# SignalRouting.net
KiCad netlist of a schematic drawn in Altium Designer
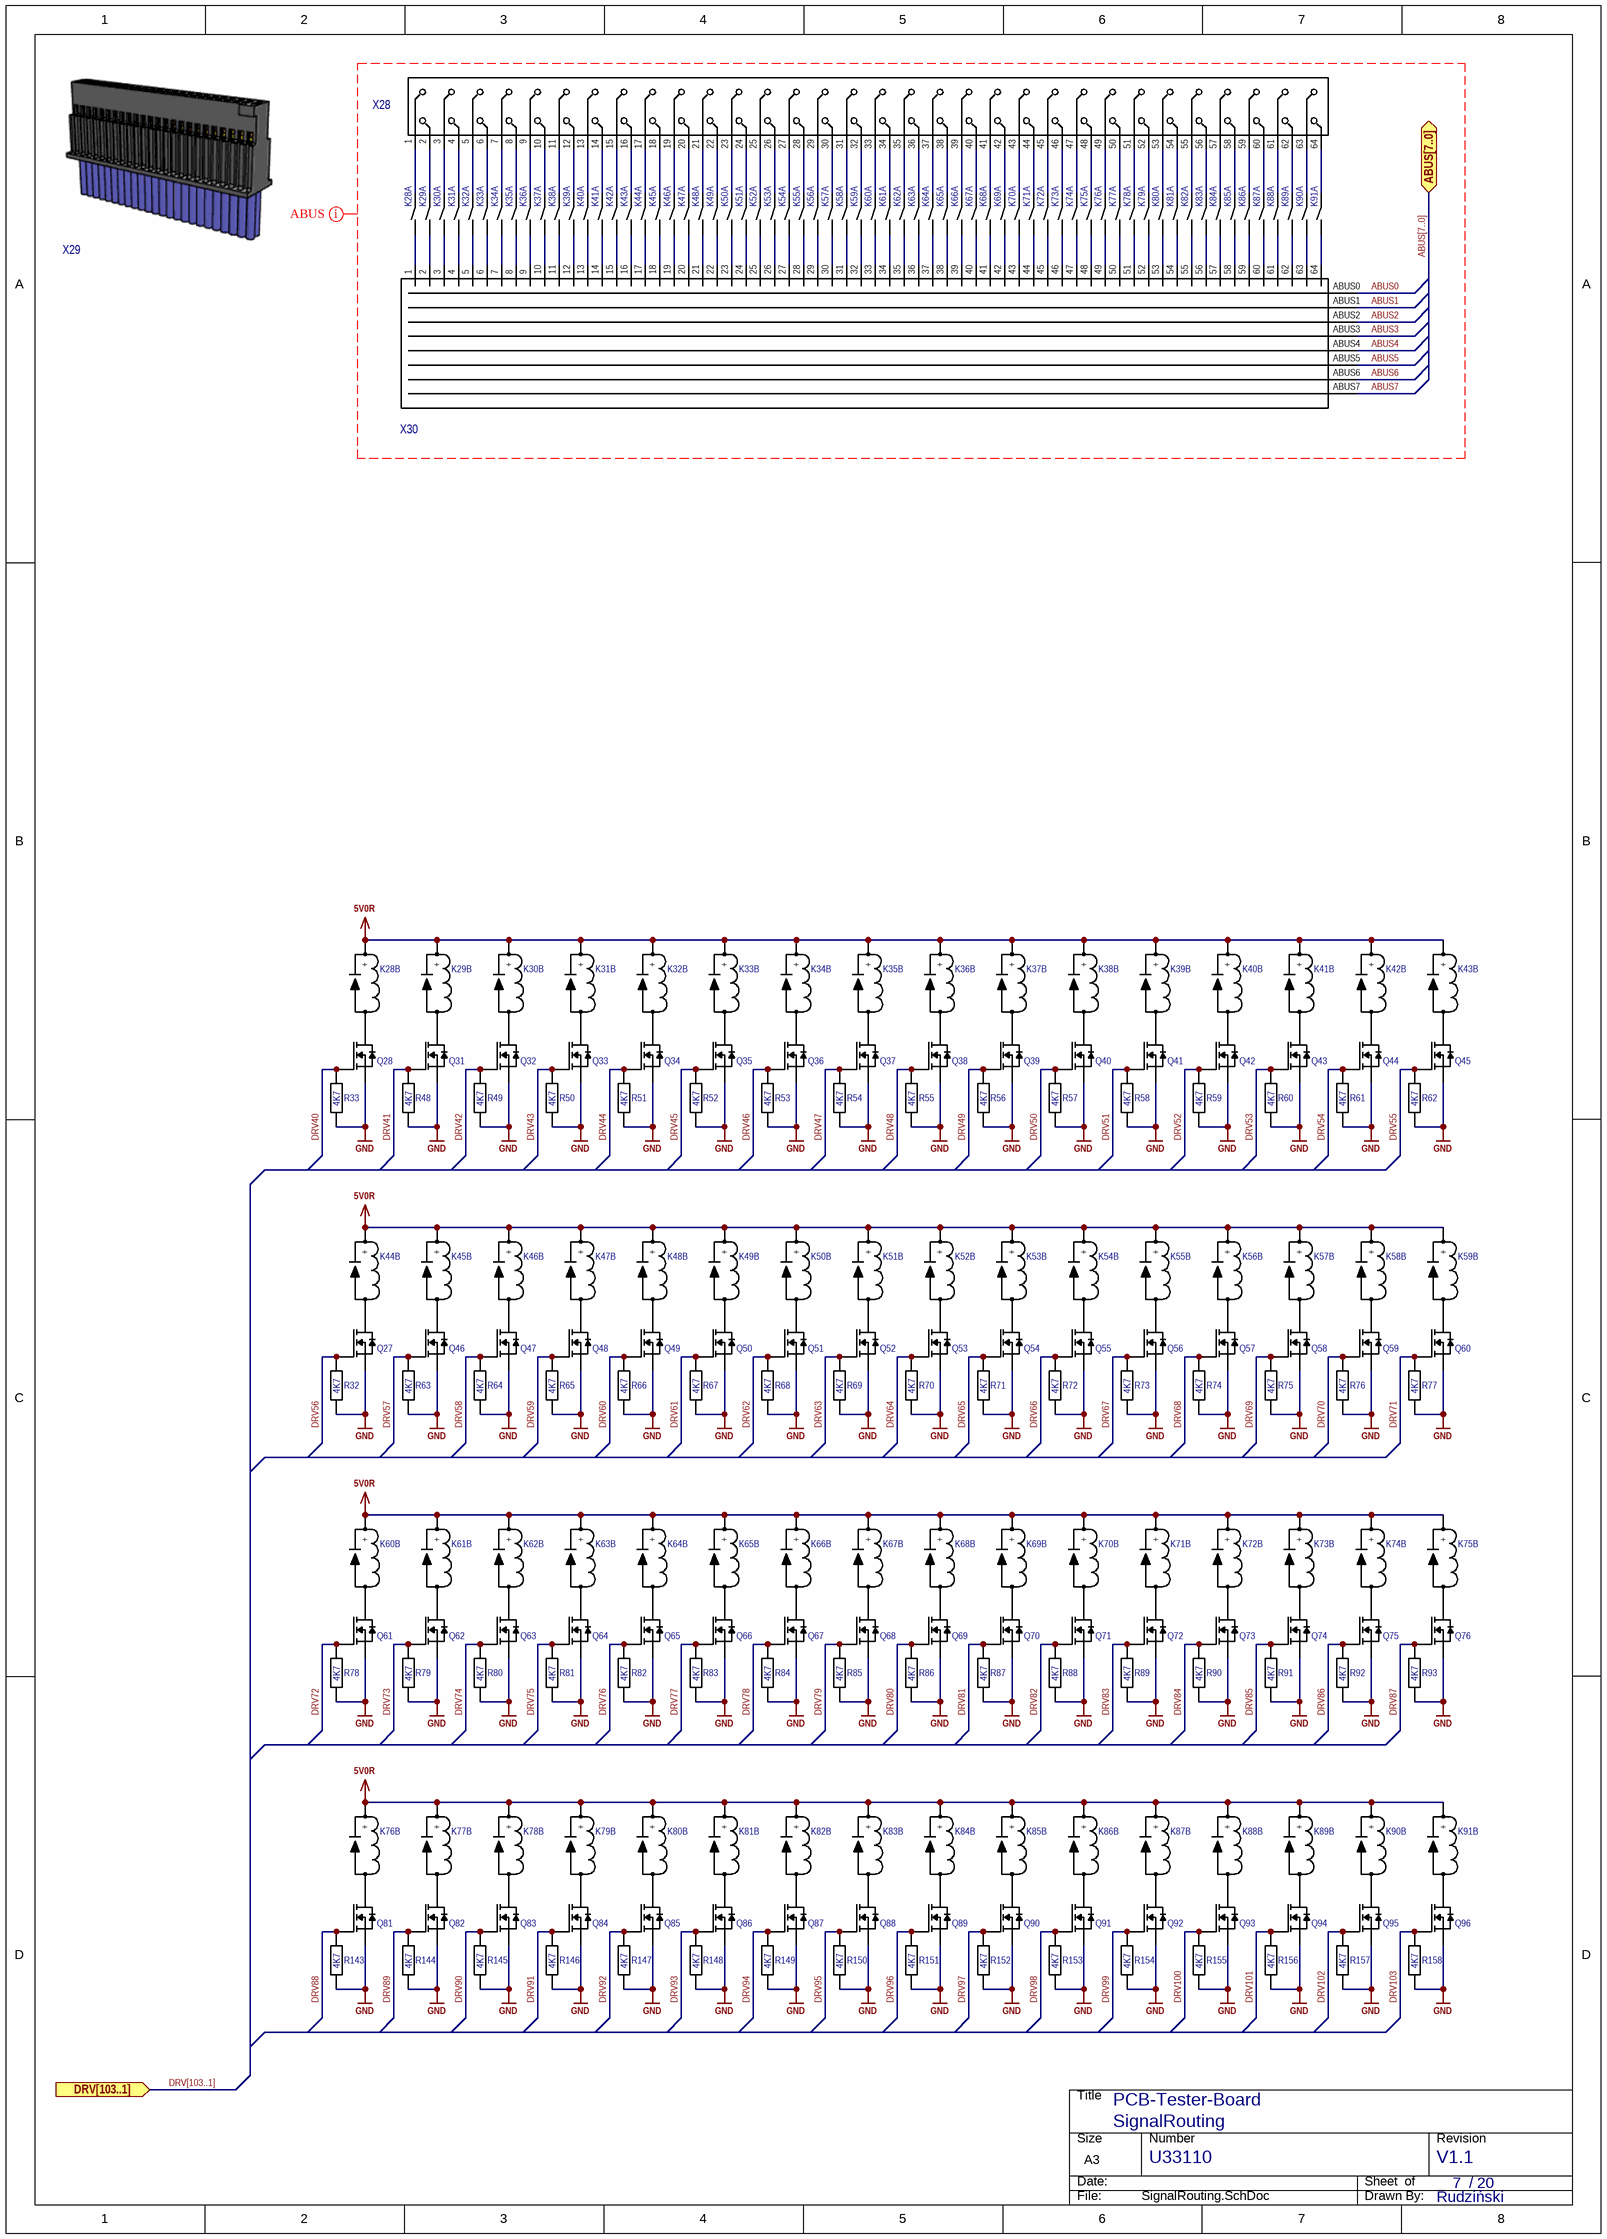
[diagram p0: SignalRouting.SchDoc]

(export (version "E")
  (design (tool "Eeschema 10.0.6"))
  (components
    (comp (ref "K28")
      (value "K")
      (footprint "118-1A")
      (description "5V Signal Relais, Normal Open")
      (fields
        (field (name "02. DISTRIBUTOR PART NUMBER") "118-1-A-5/2D")
        (field (name "13. CREATED DATE/NAME") "20.12.17 S. Kaiser")
      )
      (libsource (lib "chickenfood") (part "118-1-A-5/2D"))
    )
    (comp (ref "K29")
      (value "K")
      (footprint "118-1A")
      (description "5V Signal Relais, Normal Open")
      (fields
        (field (name "02. DISTRIBUTOR PART NUMBER") "118-1-A-5/2D")
        (field (name "13. CREATED DATE/NAME") "20.12.17 S. Kaiser")
      )
      (libsource (lib "chickenfood") (part "118-1-A-5/2D"))
    )
    (comp (ref "K30")
      (value "K")
      (footprint "118-1A")
      (description "5V Signal Relais, Normal Open")
      (fields
        (field (name "02. DISTRIBUTOR PART NUMBER") "118-1-A-5/2D")
        (field (name "13. CREATED DATE/NAME") "20.12.17 S. Kaiser")
      )
      (libsource (lib "") (part "118-1-A-5/2D_1"))
    )
    (comp (ref "K31")
      (value "K")
      (footprint "118-1A")
      (description "5V Signal Relais, Normal Open")
      (fields
        (field (name "02. DISTRIBUTOR PART NUMBER") "118-1-A-5/2D")
        (field (name "13. CREATED DATE/NAME") "20.12.17 S. Kaiser")
      )
      (libsource (lib "") (part "118-1-A-5/2D_1"))
    )
    (comp (ref "K32")
      (value "K")
      (footprint "118-1A")
      (description "5V Signal Relais, Normal Open")
      (fields
        (field (name "02. DISTRIBUTOR PART NUMBER") "118-1-A-5/2D")
        (field (name "13. CREATED DATE/NAME") "20.12.17 S. Kaiser")
      )
      (libsource (lib "") (part "118-1-A-5/2D_1"))
    )
    (comp (ref "K33")
      (value "K")
      (footprint "118-1A")
      (description "5V Signal Relais, Normal Open")
      (fields
        (field (name "02. DISTRIBUTOR PART NUMBER") "118-1-A-5/2D")
        (field (name "13. CREATED DATE/NAME") "20.12.17 S. Kaiser")
      )
      (libsource (lib "") (part "118-1-A-5/2D_1"))
    )
    (comp (ref "K34")
      (value "K")
      (footprint "118-1A")
      (description "5V Signal Relais, Normal Open")
      (fields
        (field (name "02. DISTRIBUTOR PART NUMBER") "118-1-A-5/2D")
        (field (name "13. CREATED DATE/NAME") "20.12.17 S. Kaiser")
      )
      (libsource (lib "chickenfood") (part "118-1-A-5/2D"))
    )
    (comp (ref "K35")
      (value "K")
      (footprint "118-1A")
      (description "5V Signal Relais, Normal Open")
      (fields
        (field (name "02. DISTRIBUTOR PART NUMBER") "118-1-A-5/2D")
        (field (name "13. CREATED DATE/NAME") "20.12.17 S. Kaiser")
      )
      (libsource (lib "") (part "118-1-A-5/2D_1"))
    )
    (comp (ref "K36")
      (value "K")
      (footprint "118-1A")
      (description "5V Signal Relais, Normal Open")
      (fields
        (field (name "02. DISTRIBUTOR PART NUMBER") "118-1-A-5/2D")
        (field (name "13. CREATED DATE/NAME") "20.12.17 S. Kaiser")
      )
      (libsource (lib "") (part "118-1-A-5/2D_1"))
    )
    (comp (ref "K37")
      (value "K")
      (footprint "118-1A")
      (description "5V Signal Relais, Normal Open")
      (fields
        (field (name "02. DISTRIBUTOR PART NUMBER") "118-1-A-5/2D")
        (field (name "13. CREATED DATE/NAME") "20.12.17 S. Kaiser")
      )
      (libsource (lib "chickenfood") (part "118-1-A-5/2D"))
    )
    (comp (ref "K38")
      (value "K")
      (footprint "118-1A")
      (description "5V Signal Relais, Normal Open")
      (fields
        (field (name "02. DISTRIBUTOR PART NUMBER") "118-1-A-5/2D")
        (field (name "13. CREATED DATE/NAME") "20.12.17 S. Kaiser")
      )
      (libsource (lib "") (part "118-1-A-5/2D_1"))
    )
    (comp (ref "K39")
      (value "K")
      (footprint "118-1A")
      (description "5V Signal Relais, Normal Open")
      (fields
        (field (name "02. DISTRIBUTOR PART NUMBER") "118-1-A-5/2D")
        (field (name "13. CREATED DATE/NAME") "20.12.17 S. Kaiser")
      )
      (libsource (lib "chickenfood") (part "118-1-A-5/2D"))
    )
    (comp (ref "K40")
      (value "K")
      (footprint "118-1A")
      (description "5V Signal Relais, Normal Open")
      (fields
        (field (name "02. DISTRIBUTOR PART NUMBER") "118-1-A-5/2D")
        (field (name "13. CREATED DATE/NAME") "20.12.17 S. Kaiser")
      )
      (libsource (lib "chickenfood") (part "118-1-A-5/2D"))
    )
    (comp (ref "K41")
      (value "K")
      (footprint "118-1A")
      (description "5V Signal Relais, Normal Open")
      (fields
        (field (name "02. DISTRIBUTOR PART NUMBER") "118-1-A-5/2D")
        (field (name "13. CREATED DATE/NAME") "20.12.17 S. Kaiser")
      )
      (libsource (lib "chickenfood") (part "118-1-A-5/2D"))
    )
    (comp (ref "K42")
      (value "K")
      (footprint "118-1A")
      (description "5V Signal Relais, Normal Open")
      (fields
        (field (name "02. DISTRIBUTOR PART NUMBER") "118-1-A-5/2D")
        (field (name "13. CREATED DATE/NAME") "20.12.17 S. Kaiser")
      )
      (libsource (lib "chickenfood") (part "118-1-A-5/2D"))
    )
    (comp (ref "K43")
      (value "K")
      (footprint "118-1A")
      (description "5V Signal Relais, Normal Open")
      (fields
        (field (name "02. DISTRIBUTOR PART NUMBER") "118-1-A-5/2D")
        (field (name "13. CREATED DATE/NAME") "20.12.17 S. Kaiser")
      )
      (libsource (lib "chickenfood") (part "118-1-A-5/2D"))
    )
    (comp (ref "K44")
      (value "K")
      (footprint "118-1A")
      (description "5V Signal Relais, Normal Open")
      (fields
        (field (name "02. DISTRIBUTOR PART NUMBER") "118-1-A-5/2D")
        (field (name "13. CREATED DATE/NAME") "20.12.17 S. Kaiser")
      )
      (libsource (lib "chickenfood") (part "118-1-A-5/2D"))
    )
    (comp (ref "K45")
      (value "K")
      (footprint "118-1A")
      (description "5V Signal Relais, Normal Open")
      (fields
        (field (name "02. DISTRIBUTOR PART NUMBER") "118-1-A-5/2D")
        (field (name "13. CREATED DATE/NAME") "20.12.17 S. Kaiser")
      )
      (libsource (lib "") (part "118-1-A-5/2D_1"))
    )
    (comp (ref "K46")
      (value "K")
      (footprint "118-1A")
      (description "5V Signal Relais, Normal Open")
      (fields
        (field (name "02. DISTRIBUTOR PART NUMBER") "118-1-A-5/2D")
        (field (name "13. CREATED DATE/NAME") "20.12.17 S. Kaiser")
      )
      (libsource (lib "") (part "118-1-A-5/2D_1"))
    )
    (comp (ref "K47")
      (value "K")
      (footprint "118-1A")
      (description "5V Signal Relais, Normal Open")
      (fields
        (field (name "02. DISTRIBUTOR PART NUMBER") "118-1-A-5/2D")
        (field (name "13. CREATED DATE/NAME") "20.12.17 S. Kaiser")
      )
      (libsource (lib "chickenfood") (part "118-1-A-5/2D"))
    )
    (comp (ref "K48")
      (value "K")
      (footprint "118-1A")
      (description "5V Signal Relais, Normal Open")
      (fields
        (field (name "02. DISTRIBUTOR PART NUMBER") "118-1-A-5/2D")
        (field (name "13. CREATED DATE/NAME") "20.12.17 S. Kaiser")
      )
      (libsource (lib "") (part "118-1-A-5/2D_1"))
    )
    (comp (ref "K49")
      (value "K")
      (footprint "118-1A")
      (description "5V Signal Relais, Normal Open")
      (fields
        (field (name "02. DISTRIBUTOR PART NUMBER") "118-1-A-5/2D")
        (field (name "13. CREATED DATE/NAME") "20.12.17 S. Kaiser")
      )
      (libsource (lib "chickenfood") (part "118-1-A-5/2D"))
    )
    (comp (ref "K50")
      (value "K")
      (footprint "118-1A")
      (description "5V Signal Relais, Normal Open")
      (fields
        (field (name "02. DISTRIBUTOR PART NUMBER") "118-1-A-5/2D")
        (field (name "13. CREATED DATE/NAME") "20.12.17 S. Kaiser")
      )
      (libsource (lib "chickenfood") (part "118-1-A-5/2D"))
    )
    (comp (ref "K51")
      (value "K")
      (footprint "118-1A")
      (description "5V Signal Relais, Normal Open")
      (fields
        (field (name "02. DISTRIBUTOR PART NUMBER") "118-1-A-5/2D")
        (field (name "13. CREATED DATE/NAME") "20.12.17 S. Kaiser")
      )
      (libsource (lib "") (part "118-1-A-5/2D_1"))
    )
    (comp (ref "K52")
      (value "K")
      (footprint "118-1A")
      (description "5V Signal Relais, Normal Open")
      (fields
        (field (name "02. DISTRIBUTOR PART NUMBER") "118-1-A-5/2D")
        (field (name "13. CREATED DATE/NAME") "20.12.17 S. Kaiser")
      )
      (libsource (lib "chickenfood") (part "118-1-A-5/2D"))
    )
    (comp (ref "K53")
      (value "K")
      (footprint "118-1A")
      (description "5V Signal Relais, Normal Open")
      (fields
        (field (name "02. DISTRIBUTOR PART NUMBER") "118-1-A-5/2D")
        (field (name "13. CREATED DATE/NAME") "20.12.17 S. Kaiser")
      )
      (libsource (lib "chickenfood") (part "118-1-A-5/2D"))
    )
    (comp (ref "K54")
      (value "K")
      (footprint "118-1A")
      (description "5V Signal Relais, Normal Open")
      (fields
        (field (name "02. DISTRIBUTOR PART NUMBER") "118-1-A-5/2D")
        (field (name "13. CREATED DATE/NAME") "20.12.17 S. Kaiser")
      )
      (libsource (lib "") (part "118-1-A-5/2D_1"))
    )
    (comp (ref "K55")
      (value "K")
      (footprint "118-1A")
      (description "5V Signal Relais, Normal Open")
      (fields
        (field (name "02. DISTRIBUTOR PART NUMBER") "118-1-A-5/2D")
        (field (name "13. CREATED DATE/NAME") "20.12.17 S. Kaiser")
      )
      (libsource (lib "chickenfood") (part "118-1-A-5/2D"))
    )
    (comp (ref "K56")
      (value "K")
      (footprint "118-1A")
      (description "5V Signal Relais, Normal Open")
      (fields
        (field (name "02. DISTRIBUTOR PART NUMBER") "118-1-A-5/2D")
        (field (name "13. CREATED DATE/NAME") "20.12.17 S. Kaiser")
      )
      (libsource (lib "") (part "118-1-A-5/2D_1"))
    )
    (comp (ref "K57")
      (value "K")
      (footprint "118-1A")
      (description "5V Signal Relais, Normal Open")
      (fields
        (field (name "02. DISTRIBUTOR PART NUMBER") "118-1-A-5/2D")
        (field (name "13. CREATED DATE/NAME") "20.12.17 S. Kaiser")
      )
      (libsource (lib "") (part "118-1-A-5/2D_1"))
    )
    (comp (ref "K58")
      (value "K")
      (footprint "118-1A")
      (description "5V Signal Relais, Normal Open")
      (fields
        (field (name "02. DISTRIBUTOR PART NUMBER") "118-1-A-5/2D")
        (field (name "13. CREATED DATE/NAME") "20.12.17 S. Kaiser")
      )
      (libsource (lib "chickenfood") (part "118-1-A-5/2D"))
    )
    (comp (ref "K59")
      (value "K")
      (footprint "118-1A")
      (description "5V Signal Relais, Normal Open")
      (fields
        (field (name "02. DISTRIBUTOR PART NUMBER") "118-1-A-5/2D")
        (field (name "13. CREATED DATE/NAME") "20.12.17 S. Kaiser")
      )
      (libsource (lib "chickenfood") (part "118-1-A-5/2D"))
    )
    (comp (ref "K60")
      (value "K")
      (footprint "118-1A")
      (description "5V Signal Relais, Normal Open")
      (fields
        (field (name "02. DISTRIBUTOR PART NUMBER") "118-1-A-5/2D")
        (field (name "13. CREATED DATE/NAME") "20.12.17 S. Kaiser")
      )
      (libsource (lib "") (part "118-1-A-5/2D_1"))
    )
    (comp (ref "K61")
      (value "K")
      (footprint "118-1A")
      (description "5V Signal Relais, Normal Open")
      (fields
        (field (name "02. DISTRIBUTOR PART NUMBER") "118-1-A-5/2D")
        (field (name "13. CREATED DATE/NAME") "20.12.17 S. Kaiser")
      )
      (libsource (lib "chickenfood") (part "118-1-A-5/2D"))
    )
    (comp (ref "K62")
      (value "K")
      (footprint "118-1A")
      (description "5V Signal Relais, Normal Open")
      (fields
        (field (name "02. DISTRIBUTOR PART NUMBER") "118-1-A-5/2D")
        (field (name "13. CREATED DATE/NAME") "20.12.17 S. Kaiser")
      )
      (libsource (lib "") (part "118-1-A-5/2D_1"))
    )
    (comp (ref "K63")
      (value "K")
      (footprint "118-1A")
      (description "5V Signal Relais, Normal Open")
      (fields
        (field (name "02. DISTRIBUTOR PART NUMBER") "118-1-A-5/2D")
        (field (name "13. CREATED DATE/NAME") "20.12.17 S. Kaiser")
      )
      (libsource (lib "chickenfood") (part "118-1-A-5/2D"))
    )
    (comp (ref "K64")
      (value "K")
      (footprint "118-1A")
      (description "5V Signal Relais, Normal Open")
      (fields
        (field (name "02. DISTRIBUTOR PART NUMBER") "118-1-A-5/2D")
        (field (name "13. CREATED DATE/NAME") "20.12.17 S. Kaiser")
      )
      (libsource (lib "chickenfood") (part "118-1-A-5/2D"))
    )
    (comp (ref "K65")
      (value "K")
      (footprint "118-1A")
      (description "5V Signal Relais, Normal Open")
      (fields
        (field (name "02. DISTRIBUTOR PART NUMBER") "118-1-A-5/2D")
        (field (name "13. CREATED DATE/NAME") "20.12.17 S. Kaiser")
      )
      (libsource (lib "chickenfood") (part "118-1-A-5/2D"))
    )
    (comp (ref "K66")
      (value "K")
      (footprint "118-1A")
      (description "5V Signal Relais, Normal Open")
      (fields
        (field (name "02. DISTRIBUTOR PART NUMBER") "118-1-A-5/2D")
        (field (name "13. CREATED DATE/NAME") "20.12.17 S. Kaiser")
      )
      (libsource (lib "chickenfood") (part "118-1-A-5/2D"))
    )
    (comp (ref "K67")
      (value "K")
      (footprint "118-1A")
      (description "5V Signal Relais, Normal Open")
      (fields
        (field (name "02. DISTRIBUTOR PART NUMBER") "118-1-A-5/2D")
        (field (name "13. CREATED DATE/NAME") "20.12.17 S. Kaiser")
      )
      (libsource (lib "chickenfood") (part "118-1-A-5/2D"))
    )
    (comp (ref "K68")
      (value "K")
      (footprint "118-1A")
      (description "5V Signal Relais, Normal Open")
      (fields
        (field (name "02. DISTRIBUTOR PART NUMBER") "118-1-A-5/2D")
        (field (name "13. CREATED DATE/NAME") "20.12.17 S. Kaiser")
      )
      (libsource (lib "chickenfood") (part "118-1-A-5/2D"))
    )
    (comp (ref "K69")
      (value "K")
      (footprint "118-1A")
      (description "5V Signal Relais, Normal Open")
      (fields
        (field (name "02. DISTRIBUTOR PART NUMBER") "118-1-A-5/2D")
        (field (name "13. CREATED DATE/NAME") "20.12.17 S. Kaiser")
      )
      (libsource (lib "chickenfood") (part "118-1-A-5/2D"))
    )
    (comp (ref "K70")
      (value "K")
      (footprint "118-1A")
      (description "5V Signal Relais, Normal Open")
      (fields
        (field (name "02. DISTRIBUTOR PART NUMBER") "118-1-A-5/2D")
        (field (name "13. CREATED DATE/NAME") "20.12.17 S. Kaiser")
      )
      (libsource (lib "") (part "118-1-A-5/2D_1"))
    )
    (comp (ref "K71")
      (value "K")
      (footprint "118-1A")
      (description "5V Signal Relais, Normal Open")
      (fields
        (field (name "02. DISTRIBUTOR PART NUMBER") "118-1-A-5/2D")
        (field (name "13. CREATED DATE/NAME") "20.12.17 S. Kaiser")
      )
      (libsource (lib "") (part "118-1-A-5/2D_1"))
    )
    (comp (ref "K72")
      (value "K")
      (footprint "118-1A")
      (description "5V Signal Relais, Normal Open")
      (fields
        (field (name "02. DISTRIBUTOR PART NUMBER") "118-1-A-5/2D")
        (field (name "13. CREATED DATE/NAME") "20.12.17 S. Kaiser")
      )
      (libsource (lib "") (part "118-1-A-5/2D_1"))
    )
    (comp (ref "K73")
      (value "K")
      (footprint "118-1A")
      (description "5V Signal Relais, Normal Open")
      (fields
        (field (name "02. DISTRIBUTOR PART NUMBER") "118-1-A-5/2D")
        (field (name "13. CREATED DATE/NAME") "20.12.17 S. Kaiser")
      )
      (libsource (lib "chickenfood") (part "118-1-A-5/2D"))
    )
    (comp (ref "K74")
      (value "K")
      (footprint "118-1A")
      (description "5V Signal Relais, Normal Open")
      (fields
        (field (name "02. DISTRIBUTOR PART NUMBER") "118-1-A-5/2D")
        (field (name "13. CREATED DATE/NAME") "20.12.17 S. Kaiser")
      )
      (libsource (lib "chickenfood") (part "118-1-A-5/2D"))
    )
    (comp (ref "K75")
      (value "K")
      (footprint "118-1A")
      (description "5V Signal Relais, Normal Open")
      (fields
        (field (name "02. DISTRIBUTOR PART NUMBER") "118-1-A-5/2D")
        (field (name "13. CREATED DATE/NAME") "20.12.17 S. Kaiser")
      )
      (libsource (lib "chickenfood") (part "118-1-A-5/2D"))
    )
    (comp (ref "K76")
      (value "K")
      (footprint "118-1A")
      (description "5V Signal Relais, Normal Open")
      (fields
        (field (name "02. DISTRIBUTOR PART NUMBER") "118-1-A-5/2D")
        (field (name "13. CREATED DATE/NAME") "20.12.17 S. Kaiser")
      )
      (libsource (lib "") (part "118-1-A-5/2D_1"))
    )
    (comp (ref "K77")
      (value "K")
      (footprint "118-1A")
      (description "5V Signal Relais, Normal Open")
      (fields
        (field (name "02. DISTRIBUTOR PART NUMBER") "118-1-A-5/2D")
        (field (name "13. CREATED DATE/NAME") "20.12.17 S. Kaiser")
      )
      (libsource (lib "") (part "118-1-A-5/2D_1"))
    )
    (comp (ref "K78")
      (value "K")
      (footprint "118-1A")
      (description "5V Signal Relais, Normal Open")
      (fields
        (field (name "02. DISTRIBUTOR PART NUMBER") "118-1-A-5/2D")
        (field (name "13. CREATED DATE/NAME") "20.12.17 S. Kaiser")
      )
      (libsource (lib "") (part "118-1-A-5/2D_1"))
    )
    (comp (ref "K79")
      (value "K")
      (footprint "118-1A")
      (description "5V Signal Relais, Normal Open")
      (fields
        (field (name "02. DISTRIBUTOR PART NUMBER") "118-1-A-5/2D")
        (field (name "13. CREATED DATE/NAME") "20.12.17 S. Kaiser")
      )
      (libsource (lib "chickenfood") (part "118-1-A-5/2D"))
    )
    (comp (ref "K80")
      (value "K")
      (footprint "118-1A")
      (description "5V Signal Relais, Normal Open")
      (fields
        (field (name "02. DISTRIBUTOR PART NUMBER") "118-1-A-5/2D")
        (field (name "13. CREATED DATE/NAME") "20.12.17 S. Kaiser")
      )
      (libsource (lib "") (part "118-1-A-5/2D_1"))
    )
    (comp (ref "K81")
      (value "K")
      (footprint "118-1A")
      (description "5V Signal Relais, Normal Open")
      (fields
        (field (name "02. DISTRIBUTOR PART NUMBER") "118-1-A-5/2D")
        (field (name "13. CREATED DATE/NAME") "20.12.17 S. Kaiser")
      )
      (libsource (lib "chickenfood") (part "118-1-A-5/2D"))
    )
    (comp (ref "K82")
      (value "K")
      (footprint "118-1A")
      (description "5V Signal Relais, Normal Open")
      (fields
        (field (name "02. DISTRIBUTOR PART NUMBER") "118-1-A-5/2D")
        (field (name "13. CREATED DATE/NAME") "20.12.17 S. Kaiser")
      )
      (libsource (lib "chickenfood") (part "118-1-A-5/2D"))
    )
    (comp (ref "K83")
      (value "K")
      (footprint "118-1A")
      (description "5V Signal Relais, Normal Open")
      (fields
        (field (name "02. DISTRIBUTOR PART NUMBER") "118-1-A-5/2D")
        (field (name "13. CREATED DATE/NAME") "20.12.17 S. Kaiser")
      )
      (libsource (lib "") (part "118-1-A-5/2D_1"))
    )
    (comp (ref "K84")
      (value "K")
      (footprint "118-1A")
      (description "5V Signal Relais, Normal Open")
      (fields
        (field (name "02. DISTRIBUTOR PART NUMBER") "118-1-A-5/2D")
        (field (name "13. CREATED DATE/NAME") "20.12.17 S. Kaiser")
      )
      (libsource (lib "") (part "118-1-A-5/2D_1"))
    )
    (comp (ref "K85")
      (value "K")
      (footprint "118-1A")
      (description "5V Signal Relais, Normal Open")
      (fields
        (field (name "02. DISTRIBUTOR PART NUMBER") "118-1-A-5/2D")
        (field (name "13. CREATED DATE/NAME") "20.12.17 S. Kaiser")
      )
      (libsource (lib "chickenfood") (part "118-1-A-5/2D"))
    )
    (comp (ref "K86")
      (value "K")
      (footprint "118-1A")
      (description "5V Signal Relais, Normal Open")
      (fields
        (field (name "02. DISTRIBUTOR PART NUMBER") "118-1-A-5/2D")
        (field (name "13. CREATED DATE/NAME") "20.12.17 S. Kaiser")
      )
      (libsource (lib "chickenfood") (part "118-1-A-5/2D"))
    )
    (comp (ref "K87")
      (value "K")
      (footprint "118-1A")
      (description "5V Signal Relais, Normal Open")
      (fields
        (field (name "02. DISTRIBUTOR PART NUMBER") "118-1-A-5/2D")
        (field (name "13. CREATED DATE/NAME") "20.12.17 S. Kaiser")
      )
      (libsource (lib "") (part "118-1-A-5/2D_1"))
    )
    (comp (ref "K88")
      (value "K")
      (footprint "118-1A")
      (description "5V Signal Relais, Normal Open")
      (fields
        (field (name "02. DISTRIBUTOR PART NUMBER") "118-1-A-5/2D")
        (field (name "13. CREATED DATE/NAME") "20.12.17 S. Kaiser")
      )
      (libsource (lib "") (part "118-1-A-5/2D_1"))
    )
    (comp (ref "K89")
      (value "K")
      (footprint "118-1A")
      (description "5V Signal Relais, Normal Open")
      (fields
        (field (name "02. DISTRIBUTOR PART NUMBER") "118-1-A-5/2D")
        (field (name "13. CREATED DATE/NAME") "20.12.17 S. Kaiser")
      )
      (libsource (lib "") (part "118-1-A-5/2D_1"))
    )
    (comp (ref "K90")
      (value "K")
      (footprint "118-1A")
      (description "5V Signal Relais, Normal Open")
      (fields
        (field (name "02. DISTRIBUTOR PART NUMBER") "118-1-A-5/2D")
        (field (name "13. CREATED DATE/NAME") "20.12.17 S. Kaiser")
      )
      (libsource (lib "") (part "118-1-A-5/2D_1"))
    )
    (comp (ref "K91")
      (value "K")
      (footprint "118-1A")
      (description "5V Signal Relais, Normal Open")
      (fields
        (field (name "02. DISTRIBUTOR PART NUMBER") "118-1-A-5/2D")
        (field (name "13. CREATED DATE/NAME") "20.12.17 S. Kaiser")
      )
      (libsource (lib "chickenfood") (part "118-1-A-5/2D"))
    )
    (comp (ref "Q27")
      (value "Q")
      (footprint "SOT23-3")
      (description "MOSFET N-CH 25V 680MA SOT-23")
      (fields
        (field (name "02. DISTRIBUTOR PART NUMBER") "FDV303NDKR-ND")
        (field (name "07. MANUFACTURER  PART NUMBER") "FDV303N")
        (field (name "13. CREATED DATE/NAME") "AUG 2018 / Hören")
      )
      (libsource (lib "SCT8-Board1") (part "FDV303N"))
    )
    (comp (ref "Q28")
      (value "Q")
      (footprint "SOT23-3")
      (description "MOSFET N-CH 25V 680MA SOT-23")
      (fields
        (field (name "02. DISTRIBUTOR PART NUMBER") "FDV303NDKR-ND")
        (field (name "07. MANUFACTURER  PART NUMBER") "FDV303N")
        (field (name "13. CREATED DATE/NAME") "AUG 2018 / Hören")
      )
      (libsource (lib "SCT8-Board1") (part "FDV303N"))
    )
    (comp (ref "Q31")
      (value "Q")
      (footprint "SOT23-3")
      (description "MOSFET N-CH 25V 680MA SOT-23")
      (fields
        (field (name "02. DISTRIBUTOR PART NUMBER") "FDV303NDKR-ND")
        (field (name "07. MANUFACTURER  PART NUMBER") "FDV303N")
        (field (name "13. CREATED DATE/NAME") "AUG 2018 / Hören")
      )
      (libsource (lib "SCT8-Board1") (part "FDV303N"))
    )
    (comp (ref "Q32")
      (value "Q")
      (footprint "SOT23-3")
      (description "MOSFET N-CH 25V 680MA SOT-23")
      (fields
        (field (name "02. DISTRIBUTOR PART NUMBER") "FDV303NDKR-ND")
        (field (name "07. MANUFACTURER  PART NUMBER") "FDV303N")
        (field (name "13. CREATED DATE/NAME") "AUG 2018 / Hören")
      )
      (libsource (lib "SCT8-Board1") (part "FDV303N"))
    )
    (comp (ref "Q33")
      (value "Q")
      (footprint "SOT23-3")
      (description "MOSFET N-CH 25V 680MA SOT-23")
      (fields
        (field (name "02. DISTRIBUTOR PART NUMBER") "FDV303NDKR-ND")
        (field (name "07. MANUFACTURER  PART NUMBER") "FDV303N")
        (field (name "13. CREATED DATE/NAME") "AUG 2018 / Hören")
      )
      (libsource (lib "SCT8-Board1") (part "FDV303N"))
    )
    (comp (ref "Q34")
      (value "Q")
      (footprint "SOT23-3")
      (description "MOSFET N-CH 25V 680MA SOT-23")
      (fields
        (field (name "02. DISTRIBUTOR PART NUMBER") "FDV303NDKR-ND")
        (field (name "07. MANUFACTURER  PART NUMBER") "FDV303N")
        (field (name "13. CREATED DATE/NAME") "AUG 2018 / Hören")
      )
      (libsource (lib "SCT8-Board1") (part "FDV303N"))
    )
    (comp (ref "Q35")
      (value "Q")
      (footprint "SOT23-3")
      (description "MOSFET N-CH 25V 680MA SOT-23")
      (fields
        (field (name "02. DISTRIBUTOR PART NUMBER") "FDV303NDKR-ND")
        (field (name "07. MANUFACTURER  PART NUMBER") "FDV303N")
        (field (name "13. CREATED DATE/NAME") "AUG 2018 / Hören")
      )
      (libsource (lib "SCT8-Board1") (part "FDV303N"))
    )
    (comp (ref "Q36")
      (value "Q")
      (footprint "SOT23-3")
      (description "MOSFET N-CH 25V 680MA SOT-23")
      (fields
        (field (name "02. DISTRIBUTOR PART NUMBER") "FDV303NDKR-ND")
        (field (name "07. MANUFACTURER  PART NUMBER") "FDV303N")
        (field (name "13. CREATED DATE/NAME") "AUG 2018 / Hören")
      )
      (libsource (lib "SCT8-Board1") (part "FDV303N"))
    )
    (comp (ref "Q37")
      (value "Q")
      (footprint "SOT23-3")
      (description "MOSFET N-CH 25V 680MA SOT-23")
      (fields
        (field (name "02. DISTRIBUTOR PART NUMBER") "FDV303NDKR-ND")
        (field (name "07. MANUFACTURER  PART NUMBER") "FDV303N")
        (field (name "13. CREATED DATE/NAME") "AUG 2018 / Hören")
      )
      (libsource (lib "SCT8-Board1") (part "FDV303N"))
    )
    (comp (ref "Q38")
      (value "Q")
      (footprint "SOT23-3")
      (description "MOSFET N-CH 25V 680MA SOT-23")
      (fields
        (field (name "02. DISTRIBUTOR PART NUMBER") "FDV303NDKR-ND")
        (field (name "07. MANUFACTURER  PART NUMBER") "FDV303N")
        (field (name "13. CREATED DATE/NAME") "AUG 2018 / Hören")
      )
      (libsource (lib "SCT8-Board1") (part "FDV303N"))
    )
    (comp (ref "Q39")
      (value "Q")
      (footprint "SOT23-3")
      (description "MOSFET N-CH 25V 680MA SOT-23")
      (fields
        (field (name "02. DISTRIBUTOR PART NUMBER") "FDV303NDKR-ND")
        (field (name "07. MANUFACTURER  PART NUMBER") "FDV303N")
        (field (name "13. CREATED DATE/NAME") "AUG 2018 / Hören")
      )
      (libsource (lib "SCT8-Board1") (part "FDV303N"))
    )
    (comp (ref "Q40")
      (value "Q")
      (footprint "SOT23-3")
      (description "MOSFET N-CH 25V 680MA SOT-23")
      (fields
        (field (name "02. DISTRIBUTOR PART NUMBER") "FDV303NDKR-ND")
        (field (name "07. MANUFACTURER  PART NUMBER") "FDV303N")
        (field (name "13. CREATED DATE/NAME") "AUG 2018 / Hören")
      )
      (libsource (lib "SCT8-Board1") (part "FDV303N"))
    )
    (comp (ref "Q41")
      (value "Q")
      (footprint "SOT23-3")
      (description "MOSFET N-CH 25V 680MA SOT-23")
      (fields
        (field (name "02. DISTRIBUTOR PART NUMBER") "FDV303NDKR-ND")
        (field (name "07. MANUFACTURER  PART NUMBER") "FDV303N")
        (field (name "13. CREATED DATE/NAME") "AUG 2018 / Hören")
      )
      (libsource (lib "SCT8-Board1") (part "FDV303N"))
    )
    (comp (ref "Q42")
      (value "Q")
      (footprint "SOT23-3")
      (description "MOSFET N-CH 25V 680MA SOT-23")
      (fields
        (field (name "02. DISTRIBUTOR PART NUMBER") "FDV303NDKR-ND")
        (field (name "07. MANUFACTURER  PART NUMBER") "FDV303N")
        (field (name "13. CREATED DATE/NAME") "AUG 2018 / Hören")
      )
      (libsource (lib "SCT8-Board1") (part "FDV303N"))
    )
    (comp (ref "Q43")
      (value "Q")
      (footprint "SOT23-3")
      (description "MOSFET N-CH 25V 680MA SOT-23")
      (fields
        (field (name "02. DISTRIBUTOR PART NUMBER") "FDV303NDKR-ND")
        (field (name "07. MANUFACTURER  PART NUMBER") "FDV303N")
        (field (name "13. CREATED DATE/NAME") "AUG 2018 / Hören")
      )
      (libsource (lib "SCT8-Board1") (part "FDV303N"))
    )
    (comp (ref "Q44")
      (value "Q")
      (footprint "SOT23-3")
      (description "MOSFET N-CH 25V 680MA SOT-23")
      (fields
        (field (name "02. DISTRIBUTOR PART NUMBER") "FDV303NDKR-ND")
        (field (name "07. MANUFACTURER  PART NUMBER") "FDV303N")
        (field (name "13. CREATED DATE/NAME") "AUG 2018 / Hören")
      )
      (libsource (lib "SCT8-Board1") (part "FDV303N"))
    )
    (comp (ref "Q45")
      (value "Q")
      (footprint "SOT23-3")
      (description "MOSFET N-CH 25V 680MA SOT-23")
      (fields
        (field (name "02. DISTRIBUTOR PART NUMBER") "FDV303NDKR-ND")
        (field (name "07. MANUFACTURER  PART NUMBER") "FDV303N")
        (field (name "13. CREATED DATE/NAME") "AUG 2018 / Hören")
      )
      (libsource (lib "SCT8-Board1") (part "FDV303N"))
    )
    (comp (ref "Q46")
      (value "Q")
      (footprint "SOT23-3")
      (description "MOSFET N-CH 25V 680MA SOT-23")
      (fields
        (field (name "02. DISTRIBUTOR PART NUMBER") "FDV303NDKR-ND")
        (field (name "07. MANUFACTURER  PART NUMBER") "FDV303N")
        (field (name "13. CREATED DATE/NAME") "AUG 2018 / Hören")
      )
      (libsource (lib "SCT8-Board1") (part "FDV303N"))
    )
    (comp (ref "Q47")
      (value "Q")
      (footprint "SOT23-3")
      (description "MOSFET N-CH 25V 680MA SOT-23")
      (fields
        (field (name "02. DISTRIBUTOR PART NUMBER") "FDV303NDKR-ND")
        (field (name "07. MANUFACTURER  PART NUMBER") "FDV303N")
        (field (name "13. CREATED DATE/NAME") "AUG 2018 / Hören")
      )
      (libsource (lib "SCT8-Board1") (part "FDV303N"))
    )
    (comp (ref "Q48")
      (value "Q")
      (footprint "SOT23-3")
      (description "MOSFET N-CH 25V 680MA SOT-23")
      (fields
        (field (name "02. DISTRIBUTOR PART NUMBER") "FDV303NDKR-ND")
        (field (name "07. MANUFACTURER  PART NUMBER") "FDV303N")
        (field (name "13. CREATED DATE/NAME") "AUG 2018 / Hören")
      )
      (libsource (lib "SCT8-Board1") (part "FDV303N"))
    )
    (comp (ref "Q49")
      (value "Q")
      (footprint "SOT23-3")
      (description "MOSFET N-CH 25V 680MA SOT-23")
      (fields
        (field (name "02. DISTRIBUTOR PART NUMBER") "FDV303NDKR-ND")
        (field (name "07. MANUFACTURER  PART NUMBER") "FDV303N")
        (field (name "13. CREATED DATE/NAME") "AUG 2018 / Hören")
      )
      (libsource (lib "SCT8-Board1") (part "FDV303N"))
    )
    (comp (ref "Q50")
      (value "Q")
      (footprint "SOT23-3")
      (description "MOSFET N-CH 25V 680MA SOT-23")
      (fields
        (field (name "02. DISTRIBUTOR PART NUMBER") "FDV303NDKR-ND")
        (field (name "07. MANUFACTURER  PART NUMBER") "FDV303N")
        (field (name "13. CREATED DATE/NAME") "AUG 2018 / Hören")
      )
      (libsource (lib "SCT8-Board1") (part "FDV303N"))
    )
    (comp (ref "Q51")
      (value "Q")
      (footprint "SOT23-3")
      (description "MOSFET N-CH 25V 680MA SOT-23")
      (fields
        (field (name "02. DISTRIBUTOR PART NUMBER") "FDV303NDKR-ND")
        (field (name "07. MANUFACTURER  PART NUMBER") "FDV303N")
        (field (name "13. CREATED DATE/NAME") "AUG 2018 / Hören")
      )
      (libsource (lib "SCT8-Board1") (part "FDV303N"))
    )
    (comp (ref "Q52")
      (value "Q")
      (footprint "SOT23-3")
      (description "MOSFET N-CH 25V 680MA SOT-23")
      (fields
        (field (name "02. DISTRIBUTOR PART NUMBER") "FDV303NDKR-ND")
        (field (name "07. MANUFACTURER  PART NUMBER") "FDV303N")
        (field (name "13. CREATED DATE/NAME") "AUG 2018 / Hören")
      )
      (libsource (lib "SCT8-Board1") (part "FDV303N"))
    )
    (comp (ref "Q53")
      (value "Q")
      (footprint "SOT23-3")
      (description "MOSFET N-CH 25V 680MA SOT-23")
      (fields
        (field (name "02. DISTRIBUTOR PART NUMBER") "FDV303NDKR-ND")
        (field (name "07. MANUFACTURER  PART NUMBER") "FDV303N")
        (field (name "13. CREATED DATE/NAME") "AUG 2018 / Hören")
      )
      (libsource (lib "SCT8-Board1") (part "FDV303N"))
    )
    (comp (ref "Q54")
      (value "Q")
      (footprint "SOT23-3")
      (description "MOSFET N-CH 25V 680MA SOT-23")
      (fields
        (field (name "02. DISTRIBUTOR PART NUMBER") "FDV303NDKR-ND")
        (field (name "07. MANUFACTURER  PART NUMBER") "FDV303N")
        (field (name "13. CREATED DATE/NAME") "AUG 2018 / Hören")
      )
      (libsource (lib "SCT8-Board1") (part "FDV303N"))
    )
    (comp (ref "Q55")
      (value "Q")
      (footprint "SOT23-3")
      (description "MOSFET N-CH 25V 680MA SOT-23")
      (fields
        (field (name "02. DISTRIBUTOR PART NUMBER") "FDV303NDKR-ND")
        (field (name "07. MANUFACTURER  PART NUMBER") "FDV303N")
        (field (name "13. CREATED DATE/NAME") "AUG 2018 / Hören")
      )
      (libsource (lib "SCT8-Board1") (part "FDV303N"))
    )
    (comp (ref "Q56")
      (value "Q")
      (footprint "SOT23-3")
      (description "MOSFET N-CH 25V 680MA SOT-23")
      (fields
        (field (name "02. DISTRIBUTOR PART NUMBER") "FDV303NDKR-ND")
        (field (name "07. MANUFACTURER  PART NUMBER") "FDV303N")
        (field (name "13. CREATED DATE/NAME") "AUG 2018 / Hören")
      )
      (libsource (lib "SCT8-Board1") (part "FDV303N"))
    )
    (comp (ref "Q57")
      (value "Q")
      (footprint "SOT23-3")
      (description "MOSFET N-CH 25V 680MA SOT-23")
      (fields
        (field (name "02. DISTRIBUTOR PART NUMBER") "FDV303NDKR-ND")
        (field (name "07. MANUFACTURER  PART NUMBER") "FDV303N")
        (field (name "13. CREATED DATE/NAME") "AUG 2018 / Hören")
      )
      (libsource (lib "SCT8-Board1") (part "FDV303N"))
    )
    (comp (ref "Q58")
      (value "Q")
      (footprint "SOT23-3")
      (description "MOSFET N-CH 25V 680MA SOT-23")
      (fields
        (field (name "02. DISTRIBUTOR PART NUMBER") "FDV303NDKR-ND")
        (field (name "07. MANUFACTURER  PART NUMBER") "FDV303N")
        (field (name "13. CREATED DATE/NAME") "AUG 2018 / Hören")
      )
      (libsource (lib "SCT8-Board1") (part "FDV303N"))
    )
    (comp (ref "Q59")
      (value "Q")
      (footprint "SOT23-3")
      (description "MOSFET N-CH 25V 680MA SOT-23")
      (fields
        (field (name "02. DISTRIBUTOR PART NUMBER") "FDV303NDKR-ND")
        (field (name "07. MANUFACTURER  PART NUMBER") "FDV303N")
        (field (name "13. CREATED DATE/NAME") "AUG 2018 / Hören")
      )
      (libsource (lib "SCT8-Board1") (part "FDV303N"))
    )
    (comp (ref "Q60")
      (value "Q")
      (footprint "SOT23-3")
      (description "MOSFET N-CH 25V 680MA SOT-23")
      (fields
        (field (name "02. DISTRIBUTOR PART NUMBER") "FDV303NDKR-ND")
        (field (name "07. MANUFACTURER  PART NUMBER") "FDV303N")
        (field (name "13. CREATED DATE/NAME") "AUG 2018 / Hören")
      )
      (libsource (lib "SCT8-Board1") (part "FDV303N"))
    )
    (comp (ref "Q61")
      (value "Q")
      (footprint "SOT23-3")
      (description "MOSFET N-CH 25V 680MA SOT-23")
      (fields
        (field (name "02. DISTRIBUTOR PART NUMBER") "FDV303NDKR-ND")
        (field (name "07. MANUFACTURER  PART NUMBER") "FDV303N")
        (field (name "13. CREATED DATE/NAME") "AUG 2018 / Hören")
      )
      (libsource (lib "SCT8-Board1") (part "FDV303N"))
    )
    (comp (ref "Q62")
      (value "Q")
      (footprint "SOT23-3")
      (description "MOSFET N-CH 25V 680MA SOT-23")
      (fields
        (field (name "02. DISTRIBUTOR PART NUMBER") "FDV303NDKR-ND")
        (field (name "07. MANUFACTURER  PART NUMBER") "FDV303N")
        (field (name "13. CREATED DATE/NAME") "AUG 2018 / Hören")
      )
      (libsource (lib "SCT8-Board1") (part "FDV303N"))
    )
    (comp (ref "Q63")
      (value "Q")
      (footprint "SOT23-3")
      (description "MOSFET N-CH 25V 680MA SOT-23")
      (fields
        (field (name "02. DISTRIBUTOR PART NUMBER") "FDV303NDKR-ND")
        (field (name "07. MANUFACTURER  PART NUMBER") "FDV303N")
        (field (name "13. CREATED DATE/NAME") "AUG 2018 / Hören")
      )
      (libsource (lib "SCT8-Board1") (part "FDV303N"))
    )
    (comp (ref "Q64")
      (value "Q")
      (footprint "SOT23-3")
      (description "MOSFET N-CH 25V 680MA SOT-23")
      (fields
        (field (name "02. DISTRIBUTOR PART NUMBER") "FDV303NDKR-ND")
        (field (name "07. MANUFACTURER  PART NUMBER") "FDV303N")
        (field (name "13. CREATED DATE/NAME") "AUG 2018 / Hören")
      )
      (libsource (lib "SCT8-Board1") (part "FDV303N"))
    )
    (comp (ref "Q65")
      (value "Q")
      (footprint "SOT23-3")
      (description "MOSFET N-CH 25V 680MA SOT-23")
      (fields
        (field (name "02. DISTRIBUTOR PART NUMBER") "FDV303NDKR-ND")
        (field (name "07. MANUFACTURER  PART NUMBER") "FDV303N")
        (field (name "13. CREATED DATE/NAME") "AUG 2018 / Hören")
      )
      (libsource (lib "SCT8-Board1") (part "FDV303N"))
    )
    (comp (ref "Q66")
      (value "Q")
      (footprint "SOT23-3")
      (description "MOSFET N-CH 25V 680MA SOT-23")
      (fields
        (field (name "02. DISTRIBUTOR PART NUMBER") "FDV303NDKR-ND")
        (field (name "07. MANUFACTURER  PART NUMBER") "FDV303N")
        (field (name "13. CREATED DATE/NAME") "AUG 2018 / Hören")
      )
      (libsource (lib "SCT8-Board1") (part "FDV303N"))
    )
    (comp (ref "Q67")
      (value "Q")
      (footprint "SOT23-3")
      (description "MOSFET N-CH 25V 680MA SOT-23")
      (fields
        (field (name "02. DISTRIBUTOR PART NUMBER") "FDV303NDKR-ND")
        (field (name "07. MANUFACTURER  PART NUMBER") "FDV303N")
        (field (name "13. CREATED DATE/NAME") "AUG 2018 / Hören")
      )
      (libsource (lib "SCT8-Board1") (part "FDV303N"))
    )
    (comp (ref "Q68")
      (value "Q")
      (footprint "SOT23-3")
      (description "MOSFET N-CH 25V 680MA SOT-23")
      (fields
        (field (name "02. DISTRIBUTOR PART NUMBER") "FDV303NDKR-ND")
        (field (name "07. MANUFACTURER  PART NUMBER") "FDV303N")
        (field (name "13. CREATED DATE/NAME") "AUG 2018 / Hören")
      )
      (libsource (lib "SCT8-Board1") (part "FDV303N"))
    )
    (comp (ref "Q69")
      (value "Q")
      (footprint "SOT23-3")
      (description "MOSFET N-CH 25V 680MA SOT-23")
      (fields
        (field (name "02. DISTRIBUTOR PART NUMBER") "FDV303NDKR-ND")
        (field (name "07. MANUFACTURER  PART NUMBER") "FDV303N")
        (field (name "13. CREATED DATE/NAME") "AUG 2018 / Hören")
      )
      (libsource (lib "SCT8-Board1") (part "FDV303N"))
    )
    (comp (ref "Q70")
      (value "Q")
      (footprint "SOT23-3")
      (description "MOSFET N-CH 25V 680MA SOT-23")
      (fields
        (field (name "02. DISTRIBUTOR PART NUMBER") "FDV303NDKR-ND")
        (field (name "07. MANUFACTURER  PART NUMBER") "FDV303N")
        (field (name "13. CREATED DATE/NAME") "AUG 2018 / Hören")
      )
      (libsource (lib "SCT8-Board1") (part "FDV303N"))
    )
    (comp (ref "Q71")
      (value "Q")
      (footprint "SOT23-3")
      (description "MOSFET N-CH 25V 680MA SOT-23")
      (fields
        (field (name "02. DISTRIBUTOR PART NUMBER") "FDV303NDKR-ND")
        (field (name "07. MANUFACTURER  PART NUMBER") "FDV303N")
        (field (name "13. CREATED DATE/NAME") "AUG 2018 / Hören")
      )
      (libsource (lib "SCT8-Board1") (part "FDV303N"))
    )
    (comp (ref "Q72")
      (value "Q")
      (footprint "SOT23-3")
      (description "MOSFET N-CH 25V 680MA SOT-23")
      (fields
        (field (name "02. DISTRIBUTOR PART NUMBER") "FDV303NDKR-ND")
        (field (name "07. MANUFACTURER  PART NUMBER") "FDV303N")
        (field (name "13. CREATED DATE/NAME") "AUG 2018 / Hören")
      )
      (libsource (lib "SCT8-Board1") (part "FDV303N"))
    )
    (comp (ref "Q73")
      (value "Q")
      (footprint "SOT23-3")
      (description "MOSFET N-CH 25V 680MA SOT-23")
      (fields
        (field (name "02. DISTRIBUTOR PART NUMBER") "FDV303NDKR-ND")
        (field (name "07. MANUFACTURER  PART NUMBER") "FDV303N")
        (field (name "13. CREATED DATE/NAME") "AUG 2018 / Hören")
      )
      (libsource (lib "SCT8-Board1") (part "FDV303N"))
    )
    (comp (ref "Q74")
      (value "Q")
      (footprint "SOT23-3")
      (description "MOSFET N-CH 25V 680MA SOT-23")
      (fields
        (field (name "02. DISTRIBUTOR PART NUMBER") "FDV303NDKR-ND")
        (field (name "07. MANUFACTURER  PART NUMBER") "FDV303N")
        (field (name "13. CREATED DATE/NAME") "AUG 2018 / Hören")
      )
      (libsource (lib "SCT8-Board1") (part "FDV303N"))
    )
    (comp (ref "Q75")
      (value "Q")
      (footprint "SOT23-3")
      (description "MOSFET N-CH 25V 680MA SOT-23")
      (fields
        (field (name "02. DISTRIBUTOR PART NUMBER") "FDV303NDKR-ND")
        (field (name "07. MANUFACTURER  PART NUMBER") "FDV303N")
        (field (name "13. CREATED DATE/NAME") "AUG 2018 / Hören")
      )
      (libsource (lib "SCT8-Board1") (part "FDV303N"))
    )
    (comp (ref "Q76")
      (value "Q")
      (footprint "SOT23-3")
      (description "MOSFET N-CH 25V 680MA SOT-23")
      (fields
        (field (name "02. DISTRIBUTOR PART NUMBER") "FDV303NDKR-ND")
        (field (name "07. MANUFACTURER  PART NUMBER") "FDV303N")
        (field (name "13. CREATED DATE/NAME") "AUG 2018 / Hören")
      )
      (libsource (lib "SCT8-Board1") (part "FDV303N"))
    )
    (comp (ref "Q81")
      (value "Q")
      (footprint "SOT23-3")
      (description "MOSFET N-CH 25V 680MA SOT-23")
      (fields
        (field (name "02. DISTRIBUTOR PART NUMBER") "FDV303NDKR-ND")
        (field (name "07. MANUFACTURER  PART NUMBER") "FDV303N")
        (field (name "13. CREATED DATE/NAME") "AUG 2018 / Hören")
      )
      (libsource (lib "SCT8-Board1") (part "FDV303N"))
    )
    (comp (ref "Q82")
      (value "Q")
      (footprint "SOT23-3")
      (description "MOSFET N-CH 25V 680MA SOT-23")
      (fields
        (field (name "02. DISTRIBUTOR PART NUMBER") "FDV303NDKR-ND")
        (field (name "07. MANUFACTURER  PART NUMBER") "FDV303N")
        (field (name "13. CREATED DATE/NAME") "AUG 2018 / Hören")
      )
      (libsource (lib "SCT8-Board1") (part "FDV303N"))
    )
    (comp (ref "Q83")
      (value "Q")
      (footprint "SOT23-3")
      (description "MOSFET N-CH 25V 680MA SOT-23")
      (fields
        (field (name "02. DISTRIBUTOR PART NUMBER") "FDV303NDKR-ND")
        (field (name "07. MANUFACTURER  PART NUMBER") "FDV303N")
        (field (name "13. CREATED DATE/NAME") "AUG 2018 / Hören")
      )
      (libsource (lib "SCT8-Board1") (part "FDV303N"))
    )
    (comp (ref "Q84")
      (value "Q")
      (footprint "SOT23-3")
      (description "MOSFET N-CH 25V 680MA SOT-23")
      (fields
        (field (name "02. DISTRIBUTOR PART NUMBER") "FDV303NDKR-ND")
        (field (name "07. MANUFACTURER  PART NUMBER") "FDV303N")
        (field (name "13. CREATED DATE/NAME") "AUG 2018 / Hören")
      )
      (libsource (lib "SCT8-Board1") (part "FDV303N"))
    )
    (comp (ref "Q85")
      (value "Q")
      (footprint "SOT23-3")
      (description "MOSFET N-CH 25V 680MA SOT-23")
      (fields
        (field (name "02. DISTRIBUTOR PART NUMBER") "FDV303NDKR-ND")
        (field (name "07. MANUFACTURER  PART NUMBER") "FDV303N")
        (field (name "13. CREATED DATE/NAME") "AUG 2018 / Hören")
      )
      (libsource (lib "SCT8-Board1") (part "FDV303N"))
    )
    (comp (ref "Q86")
      (value "Q")
      (footprint "SOT23-3")
      (description "MOSFET N-CH 25V 680MA SOT-23")
      (fields
        (field (name "02. DISTRIBUTOR PART NUMBER") "FDV303NDKR-ND")
        (field (name "07. MANUFACTURER  PART NUMBER") "FDV303N")
        (field (name "13. CREATED DATE/NAME") "AUG 2018 / Hören")
      )
      (libsource (lib "SCT8-Board1") (part "FDV303N"))
    )
    (comp (ref "Q87")
      (value "Q")
      (footprint "SOT23-3")
      (description "MOSFET N-CH 25V 680MA SOT-23")
      (fields
        (field (name "02. DISTRIBUTOR PART NUMBER") "FDV303NDKR-ND")
        (field (name "07. MANUFACTURER  PART NUMBER") "FDV303N")
        (field (name "13. CREATED DATE/NAME") "AUG 2018 / Hören")
      )
      (libsource (lib "SCT8-Board1") (part "FDV303N"))
    )
    (comp (ref "Q88")
      (value "Q")
      (footprint "SOT23-3")
      (description "MOSFET N-CH 25V 680MA SOT-23")
      (fields
        (field (name "02. DISTRIBUTOR PART NUMBER") "FDV303NDKR-ND")
        (field (name "07. MANUFACTURER  PART NUMBER") "FDV303N")
        (field (name "13. CREATED DATE/NAME") "AUG 2018 / Hören")
      )
      (libsource (lib "SCT8-Board1") (part "FDV303N"))
    )
    (comp (ref "Q89")
      (value "Q")
      (footprint "SOT23-3")
      (description "MOSFET N-CH 25V 680MA SOT-23")
      (fields
        (field (name "02. DISTRIBUTOR PART NUMBER") "FDV303NDKR-ND")
        (field (name "07. MANUFACTURER  PART NUMBER") "FDV303N")
        (field (name "13. CREATED DATE/NAME") "AUG 2018 / Hören")
      )
      (libsource (lib "SCT8-Board1") (part "FDV303N"))
    )
    (comp (ref "Q90")
      (value "Q")
      (footprint "SOT23-3")
      (description "MOSFET N-CH 25V 680MA SOT-23")
      (fields
        (field (name "02. DISTRIBUTOR PART NUMBER") "FDV303NDKR-ND")
        (field (name "07. MANUFACTURER  PART NUMBER") "FDV303N")
        (field (name "13. CREATED DATE/NAME") "AUG 2018 / Hören")
      )
      (libsource (lib "SCT8-Board1") (part "FDV303N"))
    )
    (comp (ref "Q91")
      (value "Q")
      (footprint "SOT23-3")
      (description "MOSFET N-CH 25V 680MA SOT-23")
      (fields
        (field (name "02. DISTRIBUTOR PART NUMBER") "FDV303NDKR-ND")
        (field (name "07. MANUFACTURER  PART NUMBER") "FDV303N")
        (field (name "13. CREATED DATE/NAME") "AUG 2018 / Hören")
      )
      (libsource (lib "SCT8-Board1") (part "FDV303N"))
    )
    (comp (ref "Q92")
      (value "Q")
      (footprint "SOT23-3")
      (description "MOSFET N-CH 25V 680MA SOT-23")
      (fields
        (field (name "02. DISTRIBUTOR PART NUMBER") "FDV303NDKR-ND")
        (field (name "07. MANUFACTURER  PART NUMBER") "FDV303N")
        (field (name "13. CREATED DATE/NAME") "AUG 2018 / Hören")
      )
      (libsource (lib "SCT8-Board1") (part "FDV303N"))
    )
    (comp (ref "Q93")
      (value "Q")
      (footprint "SOT23-3")
      (description "MOSFET N-CH 25V 680MA SOT-23")
      (fields
        (field (name "02. DISTRIBUTOR PART NUMBER") "FDV303NDKR-ND")
        (field (name "07. MANUFACTURER  PART NUMBER") "FDV303N")
        (field (name "13. CREATED DATE/NAME") "AUG 2018 / Hören")
      )
      (libsource (lib "SCT8-Board1") (part "FDV303N"))
    )
    (comp (ref "Q94")
      (value "Q")
      (footprint "SOT23-3")
      (description "MOSFET N-CH 25V 680MA SOT-23")
      (fields
        (field (name "02. DISTRIBUTOR PART NUMBER") "FDV303NDKR-ND")
        (field (name "07. MANUFACTURER  PART NUMBER") "FDV303N")
        (field (name "13. CREATED DATE/NAME") "AUG 2018 / Hören")
      )
      (libsource (lib "SCT8-Board1") (part "FDV303N"))
    )
    (comp (ref "Q95")
      (value "Q")
      (footprint "SOT23-3")
      (description "MOSFET N-CH 25V 680MA SOT-23")
      (fields
        (field (name "02. DISTRIBUTOR PART NUMBER") "FDV303NDKR-ND")
        (field (name "07. MANUFACTURER  PART NUMBER") "FDV303N")
        (field (name "13. CREATED DATE/NAME") "AUG 2018 / Hören")
      )
      (libsource (lib "SCT8-Board1") (part "FDV303N"))
    )
    (comp (ref "Q96")
      (value "Q")
      (footprint "SOT23-3")
      (description "MOSFET N-CH 25V 680MA SOT-23")
      (fields
        (field (name "02. DISTRIBUTOR PART NUMBER") "FDV303NDKR-ND")
        (field (name "07. MANUFACTURER  PART NUMBER") "FDV303N")
        (field (name "13. CREATED DATE/NAME") "AUG 2018 / Hören")
      )
      (libsource (lib "SCT8-Board1") (part "FDV303N"))
    )
    (comp (ref "R32")
      (value "4K7")
      (footprint "R0603 Reflow")
      (description "RES SMD 4.7K OHM 1% 1/10W 0603")
      (fields
        (field (name "TOLERANCE") "±1%")
        (field (name "02. DISTRIBUTOR PART NUMBER") "311-4.70KHRCT-ND")
        (field (name "13. CREATED DATE/NAME") "AUG2018/Hören")
      )
      (libsource (lib "chickenfood") (part "R"))
    )
    (comp (ref "R33")
      (value "4K7")
      (footprint "R0603 Reflow")
      (description "RES SMD 4.7K OHM 1% 1/10W 0603")
      (fields
        (field (name "TOLERANCE") "±1%")
        (field (name "02. DISTRIBUTOR PART NUMBER") "311-4.70KHRCT-ND")
        (field (name "13. CREATED DATE/NAME") "AUG2018/Hören")
      )
      (libsource (lib "chickenfood") (part "R"))
    )
    (comp (ref "R48")
      (value "4K7")
      (footprint "R0603 Reflow")
      (description "RES SMD 4.7K OHM 1% 1/10W 0603")
      (fields
        (field (name "TOLERANCE") "±1%")
        (field (name "02. DISTRIBUTOR PART NUMBER") "311-4.70KHRCT-ND")
        (field (name "13. CREATED DATE/NAME") "AUG2018/Hören")
      )
      (libsource (lib "chickenfood") (part "R"))
    )
    (comp (ref "R49")
      (value "4K7")
      (footprint "R0603 Reflow")
      (description "RES SMD 4.7K OHM 1% 1/10W 0603")
      (fields
        (field (name "TOLERANCE") "±1%")
        (field (name "02. DISTRIBUTOR PART NUMBER") "311-4.70KHRCT-ND")
        (field (name "13. CREATED DATE/NAME") "AUG2018/Hören")
      )
      (libsource (lib "chickenfood") (part "R"))
    )
    (comp (ref "R50")
      (value "4K7")
      (footprint "R0603 Reflow")
      (description "RES SMD 4.7K OHM 1% 1/10W 0603")
      (fields
        (field (name "TOLERANCE") "±1%")
        (field (name "02. DISTRIBUTOR PART NUMBER") "311-4.70KHRCT-ND")
        (field (name "13. CREATED DATE/NAME") "AUG2018/Hören")
      )
      (libsource (lib "chickenfood") (part "R"))
    )
    (comp (ref "R51")
      (value "4K7")
      (footprint "R0603 Reflow")
      (description "RES SMD 4.7K OHM 1% 1/10W 0603")
      (fields
        (field (name "TOLERANCE") "±1%")
        (field (name "02. DISTRIBUTOR PART NUMBER") "311-4.70KHRCT-ND")
        (field (name "13. CREATED DATE/NAME") "AUG2018/Hören")
      )
      (libsource (lib "chickenfood") (part "R"))
    )
    (comp (ref "R52")
      (value "4K7")
      (footprint "R0603 Reflow")
      (description "RES SMD 4.7K OHM 1% 1/10W 0603")
      (fields
        (field (name "TOLERANCE") "±1%")
        (field (name "02. DISTRIBUTOR PART NUMBER") "311-4.70KHRCT-ND")
        (field (name "13. CREATED DATE/NAME") "AUG2018/Hören")
      )
      (libsource (lib "chickenfood") (part "R"))
    )
    (comp (ref "R53")
      (value "4K7")
      (footprint "R0603 Reflow")
      (description "RES SMD 4.7K OHM 1% 1/10W 0603")
      (fields
        (field (name "TOLERANCE") "±1%")
        (field (name "02. DISTRIBUTOR PART NUMBER") "311-4.70KHRCT-ND")
        (field (name "13. CREATED DATE/NAME") "AUG2018/Hören")
      )
      (libsource (lib "chickenfood") (part "R"))
    )
    (comp (ref "R54")
      (value "4K7")
      (footprint "R0603 Reflow")
      (description "RES SMD 4.7K OHM 1% 1/10W 0603")
      (fields
        (field (name "TOLERANCE") "±1%")
        (field (name "02. DISTRIBUTOR PART NUMBER") "311-4.70KHRCT-ND")
        (field (name "13. CREATED DATE/NAME") "AUG2018/Hören")
      )
      (libsource (lib "chickenfood") (part "R"))
    )
    (comp (ref "R55")
      (value "4K7")
      (footprint "R0603 Reflow")
      (description "RES SMD 4.7K OHM 1% 1/10W 0603")
      (fields
        (field (name "TOLERANCE") "±1%")
        (field (name "02. DISTRIBUTOR PART NUMBER") "311-4.70KHRCT-ND")
        (field (name "13. CREATED DATE/NAME") "AUG2018/Hören")
      )
      (libsource (lib "chickenfood") (part "R"))
    )
    (comp (ref "R56")
      (value "4K7")
      (footprint "R0603 Reflow")
      (description "RES SMD 4.7K OHM 1% 1/10W 0603")
      (fields
        (field (name "TOLERANCE") "±1%")
        (field (name "02. DISTRIBUTOR PART NUMBER") "311-4.70KHRCT-ND")
        (field (name "13. CREATED DATE/NAME") "AUG2018/Hören")
      )
      (libsource (lib "chickenfood") (part "R"))
    )
    (comp (ref "R57")
      (value "4K7")
      (footprint "R0603 Reflow")
      (description "RES SMD 4.7K OHM 1% 1/10W 0603")
      (fields
        (field (name "TOLERANCE") "±1%")
        (field (name "02. DISTRIBUTOR PART NUMBER") "311-4.70KHRCT-ND")
        (field (name "13. CREATED DATE/NAME") "AUG2018/Hören")
      )
      (libsource (lib "chickenfood") (part "R"))
    )
    (comp (ref "R58")
      (value "4K7")
      (footprint "R0603 Reflow")
      (description "RES SMD 4.7K OHM 1% 1/10W 0603")
      (fields
        (field (name "TOLERANCE") "±1%")
        (field (name "02. DISTRIBUTOR PART NUMBER") "311-4.70KHRCT-ND")
        (field (name "13. CREATED DATE/NAME") "AUG2018/Hören")
      )
      (libsource (lib "chickenfood") (part "R"))
    )
    (comp (ref "R59")
      (value "4K7")
      (footprint "R0603 Reflow")
      (description "RES SMD 4.7K OHM 1% 1/10W 0603")
      (fields
        (field (name "TOLERANCE") "±1%")
        (field (name "02. DISTRIBUTOR PART NUMBER") "311-4.70KHRCT-ND")
        (field (name "13. CREATED DATE/NAME") "AUG2018/Hören")
      )
      (libsource (lib "chickenfood") (part "R"))
    )
    (comp (ref "R60")
      (value "4K7")
      (footprint "R0603 Reflow")
      (description "RES SMD 4.7K OHM 1% 1/10W 0603")
      (fields
        (field (name "TOLERANCE") "±1%")
        (field (name "02. DISTRIBUTOR PART NUMBER") "311-4.70KHRCT-ND")
        (field (name "13. CREATED DATE/NAME") "AUG2018/Hören")
      )
      (libsource (lib "chickenfood") (part "R"))
    )
    (comp (ref "R61")
      (value "4K7")
      (footprint "R0603 Reflow")
      (description "RES SMD 4.7K OHM 1% 1/10W 0603")
      (fields
        (field (name "TOLERANCE") "±1%")
        (field (name "02. DISTRIBUTOR PART NUMBER") "311-4.70KHRCT-ND")
        (field (name "13. CREATED DATE/NAME") "AUG2018/Hören")
      )
      (libsource (lib "chickenfood") (part "R"))
    )
    (comp (ref "R62")
      (value "4K7")
      (footprint "R0603 Reflow")
      (description "RES SMD 4.7K OHM 1% 1/10W 0603")
      (fields
        (field (name "TOLERANCE") "±1%")
        (field (name "02. DISTRIBUTOR PART NUMBER") "311-4.70KHRCT-ND")
        (field (name "13. CREATED DATE/NAME") "AUG2018/Hören")
      )
      (libsource (lib "chickenfood") (part "R"))
    )
    (comp (ref "R63")
      (value "4K7")
      (footprint "R0603 Reflow")
      (description "RES SMD 4.7K OHM 1% 1/10W 0603")
      (fields
        (field (name "TOLERANCE") "±1%")
        (field (name "02. DISTRIBUTOR PART NUMBER") "311-4.70KHRCT-ND")
        (field (name "13. CREATED DATE/NAME") "AUG2018/Hören")
      )
      (libsource (lib "chickenfood") (part "R"))
    )
    (comp (ref "R64")
      (value "4K7")
      (footprint "R0603 Reflow")
      (description "RES SMD 4.7K OHM 1% 1/10W 0603")
      (fields
        (field (name "TOLERANCE") "±1%")
        (field (name "02. DISTRIBUTOR PART NUMBER") "311-4.70KHRCT-ND")
        (field (name "13. CREATED DATE/NAME") "AUG2018/Hören")
      )
      (libsource (lib "chickenfood") (part "R"))
    )
    (comp (ref "R65")
      (value "4K7")
      (footprint "R0603 Reflow")
      (description "RES SMD 4.7K OHM 1% 1/10W 0603")
      (fields
        (field (name "TOLERANCE") "±1%")
        (field (name "02. DISTRIBUTOR PART NUMBER") "311-4.70KHRCT-ND")
        (field (name "13. CREATED DATE/NAME") "AUG2018/Hören")
      )
      (libsource (lib "chickenfood") (part "R"))
    )
    (comp (ref "R66")
      (value "4K7")
      (footprint "R0603 Reflow")
      (description "RES SMD 4.7K OHM 1% 1/10W 0603")
      (fields
        (field (name "TOLERANCE") "±1%")
        (field (name "02. DISTRIBUTOR PART NUMBER") "311-4.70KHRCT-ND")
        (field (name "13. CREATED DATE/NAME") "AUG2018/Hören")
      )
      (libsource (lib "chickenfood") (part "R"))
    )
    (comp (ref "R67")
      (value "4K7")
      (footprint "R0603 Reflow")
      (description "RES SMD 4.7K OHM 1% 1/10W 0603")
      (fields
        (field (name "TOLERANCE") "±1%")
        (field (name "02. DISTRIBUTOR PART NUMBER") "311-4.70KHRCT-ND")
        (field (name "13. CREATED DATE/NAME") "AUG2018/Hören")
      )
      (libsource (lib "chickenfood") (part "R"))
    )
    (comp (ref "R68")
      (value "4K7")
      (footprint "R0603 Reflow")
      (description "RES SMD 4.7K OHM 1% 1/10W 0603")
      (fields
        (field (name "TOLERANCE") "±1%")
        (field (name "02. DISTRIBUTOR PART NUMBER") "311-4.70KHRCT-ND")
        (field (name "13. CREATED DATE/NAME") "AUG2018/Hören")
      )
      (libsource (lib "chickenfood") (part "R"))
    )
    (comp (ref "R69")
      (value "4K7")
      (footprint "R0603 Reflow")
      (description "RES SMD 4.7K OHM 1% 1/10W 0603")
      (fields
        (field (name "TOLERANCE") "±1%")
        (field (name "02. DISTRIBUTOR PART NUMBER") "311-4.70KHRCT-ND")
        (field (name "13. CREATED DATE/NAME") "AUG2018/Hören")
      )
      (libsource (lib "chickenfood") (part "R"))
    )
    (comp (ref "R70")
      (value "4K7")
      (footprint "R0603 Reflow")
      (description "RES SMD 4.7K OHM 1% 1/10W 0603")
      (fields
        (field (name "TOLERANCE") "±1%")
        (field (name "02. DISTRIBUTOR PART NUMBER") "311-4.70KHRCT-ND")
        (field (name "13. CREATED DATE/NAME") "AUG2018/Hören")
      )
      (libsource (lib "chickenfood") (part "R"))
    )
    (comp (ref "R71")
      (value "4K7")
      (footprint "R0603 Reflow")
      (description "RES SMD 4.7K OHM 1% 1/10W 0603")
      (fields
        (field (name "TOLERANCE") "±1%")
        (field (name "02. DISTRIBUTOR PART NUMBER") "311-4.70KHRCT-ND")
        (field (name "13. CREATED DATE/NAME") "AUG2018/Hören")
      )
      (libsource (lib "chickenfood") (part "R"))
    )
    (comp (ref "R72")
      (value "4K7")
      (footprint "R0603 Reflow")
      (description "RES SMD 4.7K OHM 1% 1/10W 0603")
      (fields
        (field (name "TOLERANCE") "±1%")
        (field (name "02. DISTRIBUTOR PART NUMBER") "311-4.70KHRCT-ND")
        (field (name "13. CREATED DATE/NAME") "AUG2018/Hören")
      )
      (libsource (lib "chickenfood") (part "R"))
    )
    (comp (ref "R73")
      (value "4K7")
      (footprint "R0603 Reflow")
      (description "RES SMD 4.7K OHM 1% 1/10W 0603")
      (fields
        (field (name "TOLERANCE") "±1%")
        (field (name "02. DISTRIBUTOR PART NUMBER") "311-4.70KHRCT-ND")
        (field (name "13. CREATED DATE/NAME") "AUG2018/Hören")
      )
      (libsource (lib "chickenfood") (part "R"))
    )
    (comp (ref "R74")
      (value "4K7")
      (footprint "R0603 Reflow")
      (description "RES SMD 4.7K OHM 1% 1/10W 0603")
      (fields
        (field (name "TOLERANCE") "±1%")
        (field (name "02. DISTRIBUTOR PART NUMBER") "311-4.70KHRCT-ND")
        (field (name "13. CREATED DATE/NAME") "AUG2018/Hören")
      )
      (libsource (lib "chickenfood") (part "R"))
    )
    (comp (ref "R75")
      (value "4K7")
      (footprint "R0603 Reflow")
      (description "RES SMD 4.7K OHM 1% 1/10W 0603")
      (fields
        (field (name "TOLERANCE") "±1%")
        (field (name "02. DISTRIBUTOR PART NUMBER") "311-4.70KHRCT-ND")
        (field (name "13. CREATED DATE/NAME") "AUG2018/Hören")
      )
      (libsource (lib "chickenfood") (part "R"))
    )
    (comp (ref "R76")
      (value "4K7")
      (footprint "R0603 Reflow")
      (description "RES SMD 4.7K OHM 1% 1/10W 0603")
      (fields
        (field (name "TOLERANCE") "±1%")
        (field (name "02. DISTRIBUTOR PART NUMBER") "311-4.70KHRCT-ND")
        (field (name "13. CREATED DATE/NAME") "AUG2018/Hören")
      )
      (libsource (lib "chickenfood") (part "R"))
    )
    (comp (ref "R77")
      (value "4K7")
      (footprint "R0603 Reflow")
      (description "RES SMD 4.7K OHM 1% 1/10W 0603")
      (fields
        (field (name "TOLERANCE") "±1%")
        (field (name "02. DISTRIBUTOR PART NUMBER") "311-4.70KHRCT-ND")
        (field (name "13. CREATED DATE/NAME") "AUG2018/Hören")
      )
      (libsource (lib "chickenfood") (part "R"))
    )
    (comp (ref "R78")
      (value "4K7")
      (footprint "R0603 Reflow")
      (description "RES SMD 4.7K OHM 1% 1/10W 0603")
      (fields
        (field (name "TOLERANCE") "±1%")
        (field (name "02. DISTRIBUTOR PART NUMBER") "311-4.70KHRCT-ND")
        (field (name "13. CREATED DATE/NAME") "AUG2018/Hören")
      )
      (libsource (lib "chickenfood") (part "R"))
    )
    (comp (ref "R79")
      (value "4K7")
      (footprint "R0603 Reflow")
      (description "RES SMD 4.7K OHM 1% 1/10W 0603")
      (fields
        (field (name "TOLERANCE") "±1%")
        (field (name "02. DISTRIBUTOR PART NUMBER") "311-4.70KHRCT-ND")
        (field (name "13. CREATED DATE/NAME") "AUG2018/Hören")
      )
      (libsource (lib "chickenfood") (part "R"))
    )
    (comp (ref "R80")
      (value "4K7")
      (footprint "R0603 Reflow")
      (description "RES SMD 4.7K OHM 1% 1/10W 0603")
      (fields
        (field (name "TOLERANCE") "±1%")
        (field (name "02. DISTRIBUTOR PART NUMBER") "311-4.70KHRCT-ND")
        (field (name "13. CREATED DATE/NAME") "AUG2018/Hören")
      )
      (libsource (lib "chickenfood") (part "R"))
    )
    (comp (ref "R81")
      (value "4K7")
      (footprint "R0603 Reflow")
      (description "RES SMD 4.7K OHM 1% 1/10W 0603")
      (fields
        (field (name "TOLERANCE") "±1%")
        (field (name "02. DISTRIBUTOR PART NUMBER") "311-4.70KHRCT-ND")
        (field (name "13. CREATED DATE/NAME") "AUG2018/Hören")
      )
      (libsource (lib "chickenfood") (part "R"))
    )
    (comp (ref "R82")
      (value "4K7")
      (footprint "R0603 Reflow")
      (description "RES SMD 4.7K OHM 1% 1/10W 0603")
      (fields
        (field (name "TOLERANCE") "±1%")
        (field (name "02. DISTRIBUTOR PART NUMBER") "311-4.70KHRCT-ND")
        (field (name "13. CREATED DATE/NAME") "AUG2018/Hören")
      )
      (libsource (lib "chickenfood") (part "R"))
    )
    (comp (ref "R83")
      (value "4K7")
      (footprint "R0603 Reflow")
      (description "RES SMD 4.7K OHM 1% 1/10W 0603")
      (fields
        (field (name "TOLERANCE") "±1%")
        (field (name "02. DISTRIBUTOR PART NUMBER") "311-4.70KHRCT-ND")
        (field (name "13. CREATED DATE/NAME") "AUG2018/Hören")
      )
      (libsource (lib "chickenfood") (part "R"))
    )
    (comp (ref "R84")
      (value "4K7")
      (footprint "R0603 Reflow")
      (description "RES SMD 4.7K OHM 1% 1/10W 0603")
      (fields
        (field (name "TOLERANCE") "±1%")
        (field (name "02. DISTRIBUTOR PART NUMBER") "311-4.70KHRCT-ND")
        (field (name "13. CREATED DATE/NAME") "AUG2018/Hören")
      )
      (libsource (lib "chickenfood") (part "R"))
    )
    (comp (ref "R85")
      (value "4K7")
      (footprint "R0603 Reflow")
      (description "RES SMD 4.7K OHM 1% 1/10W 0603")
      (fields
        (field (name "TOLERANCE") "±1%")
        (field (name "02. DISTRIBUTOR PART NUMBER") "311-4.70KHRCT-ND")
        (field (name "13. CREATED DATE/NAME") "AUG2018/Hören")
      )
      (libsource (lib "chickenfood") (part "R"))
    )
    (comp (ref "R86")
      (value "4K7")
      (footprint "R0603 Reflow")
      (description "RES SMD 4.7K OHM 1% 1/10W 0603")
      (fields
        (field (name "TOLERANCE") "±1%")
        (field (name "02. DISTRIBUTOR PART NUMBER") "311-4.70KHRCT-ND")
        (field (name "13. CREATED DATE/NAME") "AUG2018/Hören")
      )
      (libsource (lib "chickenfood") (part "R"))
    )
    (comp (ref "R87")
      (value "4K7")
      (footprint "R0603 Reflow")
      (description "RES SMD 4.7K OHM 1% 1/10W 0603")
      (fields
        (field (name "TOLERANCE") "±1%")
        (field (name "02. DISTRIBUTOR PART NUMBER") "311-4.70KHRCT-ND")
        (field (name "13. CREATED DATE/NAME") "AUG2018/Hören")
      )
      (libsource (lib "chickenfood") (part "R"))
    )
    (comp (ref "R88")
      (value "4K7")
      (footprint "R0603 Reflow")
      (description "RES SMD 4.7K OHM 1% 1/10W 0603")
      (fields
        (field (name "TOLERANCE") "±1%")
        (field (name "02. DISTRIBUTOR PART NUMBER") "311-4.70KHRCT-ND")
        (field (name "13. CREATED DATE/NAME") "AUG2018/Hören")
      )
      (libsource (lib "chickenfood") (part "R"))
    )
    (comp (ref "R89")
      (value "4K7")
      (footprint "R0603 Reflow")
      (description "RES SMD 4.7K OHM 1% 1/10W 0603")
      (fields
        (field (name "TOLERANCE") "±1%")
        (field (name "02. DISTRIBUTOR PART NUMBER") "311-4.70KHRCT-ND")
        (field (name "13. CREATED DATE/NAME") "AUG2018/Hören")
      )
      (libsource (lib "chickenfood") (part "R"))
    )
    (comp (ref "R90")
      (value "4K7")
      (footprint "R0603 Reflow")
      (description "RES SMD 4.7K OHM 1% 1/10W 0603")
      (fields
        (field (name "TOLERANCE") "±1%")
        (field (name "02. DISTRIBUTOR PART NUMBER") "311-4.70KHRCT-ND")
        (field (name "13. CREATED DATE/NAME") "AUG2018/Hören")
      )
      (libsource (lib "chickenfood") (part "R"))
    )
    (comp (ref "R91")
      (value "4K7")
      (footprint "R0603 Reflow")
      (description "RES SMD 4.7K OHM 1% 1/10W 0603")
      (fields
        (field (name "TOLERANCE") "±1%")
        (field (name "02. DISTRIBUTOR PART NUMBER") "311-4.70KHRCT-ND")
        (field (name "13. CREATED DATE/NAME") "AUG2018/Hören")
      )
      (libsource (lib "chickenfood") (part "R"))
    )
    (comp (ref "R92")
      (value "4K7")
      (footprint "R0603 Reflow")
      (description "RES SMD 4.7K OHM 1% 1/10W 0603")
      (fields
        (field (name "TOLERANCE") "±1%")
        (field (name "02. DISTRIBUTOR PART NUMBER") "311-4.70KHRCT-ND")
        (field (name "13. CREATED DATE/NAME") "AUG2018/Hören")
      )
      (libsource (lib "chickenfood") (part "R"))
    )
    (comp (ref "R93")
      (value "4K7")
      (footprint "R0603 Reflow")
      (description "RES SMD 4.7K OHM 1% 1/10W 0603")
      (fields
        (field (name "TOLERANCE") "±1%")
        (field (name "02. DISTRIBUTOR PART NUMBER") "311-4.70KHRCT-ND")
        (field (name "13. CREATED DATE/NAME") "AUG2018/Hören")
      )
      (libsource (lib "chickenfood") (part "R"))
    )
    (comp (ref "R143")
      (value "4K7")
      (footprint "R0603 Reflow")
      (description "RES SMD 4.7K OHM 1% 1/10W 0603")
      (fields
        (field (name "TOLERANCE") "±1%")
        (field (name "02. DISTRIBUTOR PART NUMBER") "311-4.70KHRCT-ND")
        (field (name "13. CREATED DATE/NAME") "AUG2018/Hören")
      )
      (libsource (lib "chickenfood") (part "R"))
    )
    (comp (ref "R144")
      (value "4K7")
      (footprint "R0603 Reflow")
      (description "RES SMD 4.7K OHM 1% 1/10W 0603")
      (fields
        (field (name "TOLERANCE") "±1%")
        (field (name "02. DISTRIBUTOR PART NUMBER") "311-4.70KHRCT-ND")
        (field (name "13. CREATED DATE/NAME") "AUG2018/Hören")
      )
      (libsource (lib "chickenfood") (part "R"))
    )
    (comp (ref "R145")
      (value "4K7")
      (footprint "R0603 Reflow")
      (description "RES SMD 4.7K OHM 1% 1/10W 0603")
      (fields
        (field (name "TOLERANCE") "±1%")
        (field (name "02. DISTRIBUTOR PART NUMBER") "311-4.70KHRCT-ND")
        (field (name "13. CREATED DATE/NAME") "AUG2018/Hören")
      )
      (libsource (lib "chickenfood") (part "R"))
    )
    (comp (ref "R146")
      (value "4K7")
      (footprint "R0603 Reflow")
      (description "RES SMD 4.7K OHM 1% 1/10W 0603")
      (fields
        (field (name "TOLERANCE") "±1%")
        (field (name "02. DISTRIBUTOR PART NUMBER") "311-4.70KHRCT-ND")
        (field (name "13. CREATED DATE/NAME") "AUG2018/Hören")
      )
      (libsource (lib "chickenfood") (part "R"))
    )
    (comp (ref "R147")
      (value "4K7")
      (footprint "R0603 Reflow")
      (description "RES SMD 4.7K OHM 1% 1/10W 0603")
      (fields
        (field (name "TOLERANCE") "±1%")
        (field (name "02. DISTRIBUTOR PART NUMBER") "311-4.70KHRCT-ND")
        (field (name "13. CREATED DATE/NAME") "AUG2018/Hören")
      )
      (libsource (lib "chickenfood") (part "R"))
    )
    (comp (ref "R148")
      (value "4K7")
      (footprint "R0603 Reflow")
      (description "RES SMD 4.7K OHM 1% 1/10W 0603")
      (fields
        (field (name "TOLERANCE") "±1%")
        (field (name "02. DISTRIBUTOR PART NUMBER") "311-4.70KHRCT-ND")
        (field (name "13. CREATED DATE/NAME") "AUG2018/Hören")
      )
      (libsource (lib "chickenfood") (part "R"))
    )
    (comp (ref "R149")
      (value "4K7")
      (footprint "R0603 Reflow")
      (description "RES SMD 4.7K OHM 1% 1/10W 0603")
      (fields
        (field (name "TOLERANCE") "±1%")
        (field (name "02. DISTRIBUTOR PART NUMBER") "311-4.70KHRCT-ND")
        (field (name "13. CREATED DATE/NAME") "AUG2018/Hören")
      )
      (libsource (lib "chickenfood") (part "R"))
    )
    (comp (ref "R150")
      (value "4K7")
      (footprint "R0603 Reflow")
      (description "RES SMD 4.7K OHM 1% 1/10W 0603")
      (fields
        (field (name "TOLERANCE") "±1%")
        (field (name "02. DISTRIBUTOR PART NUMBER") "311-4.70KHRCT-ND")
        (field (name "13. CREATED DATE/NAME") "AUG2018/Hören")
      )
      (libsource (lib "chickenfood") (part "R"))
    )
    (comp (ref "R151")
      (value "4K7")
      (footprint "R0603 Reflow")
      (description "RES SMD 4.7K OHM 1% 1/10W 0603")
      (fields
        (field (name "TOLERANCE") "±1%")
        (field (name "02. DISTRIBUTOR PART NUMBER") "311-4.70KHRCT-ND")
        (field (name "13. CREATED DATE/NAME") "AUG2018/Hören")
      )
      (libsource (lib "chickenfood") (part "R"))
    )
    (comp (ref "R152")
      (value "4K7")
      (footprint "R0603 Reflow")
      (description "RES SMD 4.7K OHM 1% 1/10W 0603")
      (fields
        (field (name "TOLERANCE") "±1%")
        (field (name "02. DISTRIBUTOR PART NUMBER") "311-4.70KHRCT-ND")
        (field (name "13. CREATED DATE/NAME") "AUG2018/Hören")
      )
      (libsource (lib "chickenfood") (part "R"))
    )
    (comp (ref "R153")
      (value "4K7")
      (footprint "R0603 Reflow")
      (description "RES SMD 4.7K OHM 1% 1/10W 0603")
      (fields
        (field (name "TOLERANCE") "±1%")
        (field (name "02. DISTRIBUTOR PART NUMBER") "311-4.70KHRCT-ND")
        (field (name "13. CREATED DATE/NAME") "AUG2018/Hören")
      )
      (libsource (lib "chickenfood") (part "R"))
    )
    (comp (ref "R154")
      (value "4K7")
      (footprint "R0603 Reflow")
      (description "RES SMD 4.7K OHM 1% 1/10W 0603")
      (fields
        (field (name "TOLERANCE") "±1%")
        (field (name "02. DISTRIBUTOR PART NUMBER") "311-4.70KHRCT-ND")
        (field (name "13. CREATED DATE/NAME") "AUG2018/Hören")
      )
      (libsource (lib "chickenfood") (part "R"))
    )
    (comp (ref "R155")
      (value "4K7")
      (footprint "R0603 Reflow")
      (description "RES SMD 4.7K OHM 1% 1/10W 0603")
      (fields
        (field (name "TOLERANCE") "±1%")
        (field (name "02. DISTRIBUTOR PART NUMBER") "311-4.70KHRCT-ND")
        (field (name "13. CREATED DATE/NAME") "AUG2018/Hören")
      )
      (libsource (lib "chickenfood") (part "R"))
    )
    (comp (ref "R156")
      (value "4K7")
      (footprint "R0603 Reflow")
      (description "RES SMD 4.7K OHM 1% 1/10W 0603")
      (fields
        (field (name "TOLERANCE") "±1%")
        (field (name "02. DISTRIBUTOR PART NUMBER") "311-4.70KHRCT-ND")
        (field (name "13. CREATED DATE/NAME") "AUG2018/Hören")
      )
      (libsource (lib "chickenfood") (part "R"))
    )
    (comp (ref "R157")
      (value "4K7")
      (footprint "R0603 Reflow")
      (description "RES SMD 4.7K OHM 1% 1/10W 0603")
      (fields
        (field (name "TOLERANCE") "±1%")
        (field (name "02. DISTRIBUTOR PART NUMBER") "311-4.70KHRCT-ND")
        (field (name "13. CREATED DATE/NAME") "AUG2018/Hören")
      )
      (libsource (lib "chickenfood") (part "R"))
    )
    (comp (ref "R158")
      (value "4K7")
      (footprint "R0603 Reflow")
      (description "RES SMD 4.7K OHM 1% 1/10W 0603")
      (fields
        (field (name "TOLERANCE") "±1%")
        (field (name "02. DISTRIBUTOR PART NUMBER") "311-4.70KHRCT-ND")
        (field (name "13. CREATED DATE/NAME") "AUG2018/Hören")
      )
      (libsource (lib "chickenfood") (part "R"))
    )
    (comp (ref "X28")
      (value "X")
      (footprint "TFC-132-01-F-D-LA")
      (description "CONN HEADER TH Straight 64POS 1.27MM")
      (fields
        (field (name "02. DISTRIBUTOR PART NUMBER") "TFC-132-01-F-D-LC")
        (field (name "13. CREATED DATE/NAME") "??? / Hören")
      )
      (libsource (lib "PCB-Tester-Board-V1") (part "TFC-132-01-F-D-LA"))
    )
    (comp (ref "X29")
      (value "X")
      (description "32 x 2 x 1.27mm SOCKET DISCRETE CABL COLORED")
      (fields
        (field (name "02. DISTRIBUTOR PART NUMBER") "SFSD-32-30C-G-15.00-S")
        (field (name "13. CREATED DATE/NAME") "??? / Hören")
      )
      (libsource (lib "PCB-Tester-Board-V1") (part "SFSD-32-30C-G-15.00-S"))
    )
    (comp (ref "X30")
      (value "X")
      (footprint "CONFIG64")
      (description "PCB Tester Configuration Matrix for 64 Relays over 8 ABUSes")
      (fields (field (name "13. CREATED DATE/NAME") "??? / Hören"))
      (libsource (lib "PCB-Tester-Board-V1") (part "CONFIG64"))
    )
  )
  (nets
    (net (code "40") (name "/ABUS0") (class "Default")
      (node (ref "X30") (pin "ABUS0") (pinfunction "ABUS0_ABUS0") (pintype "passive"))
    )
    (net (code "41") (name "/ABUS1") (class "Default")
      (node (ref "X30") (pin "ABUS1") (pinfunction "ABUS1_ABUS1") (pintype "passive"))
    )
    (net (code "42") (name "/ABUS2") (class "Default")
      (node (ref "X30") (pin "ABUS2") (pinfunction "ABUS2_ABUS2") (pintype "passive"))
    )
    (net (code "43") (name "/ABUS3") (class "Default")
      (node (ref "X30") (pin "ABUS3") (pinfunction "ABUS3_ABUS3") (pintype "passive"))
    )
    (net (code "44") (name "/ABUS4") (class "Default")
      (node (ref "X30") (pin "ABUS4") (pinfunction "ABUS4_ABUS4") (pintype "passive"))
    )
    (net (code "45") (name "/ABUS5") (class "Default")
      (node (ref "X30") (pin "ABUS5") (pinfunction "ABUS5_ABUS5") (pintype "passive"))
    )
    (net (code "46") (name "/ABUS6") (class "Default")
      (node (ref "X30") (pin "ABUS6") (pinfunction "ABUS6_ABUS6") (pintype "passive"))
    )
    (net (code "47") (name "/ABUS7") (class "Default")
      (node (ref "X30") (pin "ABUS7") (pinfunction "ABUS7_ABUS7") (pintype "passive"))
    )
    (net (code "49") (name "/DRV40") (class "Default")
      (node (ref "Q28") (pin "1") (pinfunction "G_1") (pintype "passive"))
      (node (ref "R33") (pin "2") (pinfunction "2_2") (pintype "passive"))
    )
    (net (code "50") (name "/DRV41") (class "Default")
      (node (ref "Q31") (pin "1") (pinfunction "G_1") (pintype "passive"))
      (node (ref "R48") (pin "2") (pinfunction "2_2") (pintype "passive"))
    )
    (net (code "51") (name "/DRV42") (class "Default")
      (node (ref "Q32") (pin "1") (pinfunction "G_1") (pintype "passive"))
      (node (ref "R49") (pin "2") (pinfunction "2_2") (pintype "passive"))
    )
    (net (code "52") (name "/DRV43") (class "Default")
      (node (ref "Q33") (pin "1") (pinfunction "G_1") (pintype "passive"))
      (node (ref "R50") (pin "2") (pinfunction "2_2") (pintype "passive"))
    )
    (net (code "53") (name "/DRV44") (class "Default")
      (node (ref "Q34") (pin "1") (pinfunction "G_1") (pintype "passive"))
      (node (ref "R51") (pin "2") (pinfunction "2_2") (pintype "passive"))
    )
    (net (code "54") (name "/DRV45") (class "Default")
      (node (ref "Q35") (pin "1") (pinfunction "G_1") (pintype "passive"))
      (node (ref "R52") (pin "2") (pinfunction "2_2") (pintype "passive"))
    )
    (net (code "55") (name "/DRV46") (class "Default")
      (node (ref "Q36") (pin "1") (pinfunction "G_1") (pintype "passive"))
      (node (ref "R53") (pin "2") (pinfunction "2_2") (pintype "passive"))
    )
    (net (code "56") (name "/DRV47") (class "Default")
      (node (ref "Q37") (pin "1") (pinfunction "G_1") (pintype "passive"))
      (node (ref "R54") (pin "2") (pinfunction "2_2") (pintype "passive"))
    )
    (net (code "57") (name "/DRV48") (class "Default")
      (node (ref "Q38") (pin "1") (pinfunction "G_1") (pintype "passive"))
      (node (ref "R55") (pin "2") (pinfunction "2_2") (pintype "passive"))
    )
    (net (code "58") (name "/DRV49") (class "Default")
      (node (ref "Q39") (pin "1") (pinfunction "G_1") (pintype "passive"))
      (node (ref "R56") (pin "2") (pinfunction "2_2") (pintype "passive"))
    )
    (net (code "59") (name "/DRV50") (class "Default")
      (node (ref "Q40") (pin "1") (pinfunction "G_1") (pintype "passive"))
      (node (ref "R57") (pin "2") (pinfunction "2_2") (pintype "passive"))
    )
    (net (code "60") (name "/DRV51") (class "Default")
      (node (ref "Q41") (pin "1") (pinfunction "G_1") (pintype "passive"))
      (node (ref "R58") (pin "2") (pinfunction "2_2") (pintype "passive"))
    )
    (net (code "61") (name "/DRV52") (class "Default")
      (node (ref "Q42") (pin "1") (pinfunction "G_1") (pintype "passive"))
      (node (ref "R59") (pin "2") (pinfunction "2_2") (pintype "passive"))
    )
    (net (code "62") (name "/DRV53") (class "Default")
      (node (ref "Q43") (pin "1") (pinfunction "G_1") (pintype "passive"))
      (node (ref "R60") (pin "2") (pinfunction "2_2") (pintype "passive"))
    )
    (net (code "63") (name "/DRV54") (class "Default")
      (node (ref "Q44") (pin "1") (pinfunction "G_1") (pintype "passive"))
      (node (ref "R61") (pin "2") (pinfunction "2_2") (pintype "passive"))
    )
    (net (code "64") (name "/DRV55") (class "Default")
      (node (ref "Q45") (pin "1") (pinfunction "G_1") (pintype "passive"))
      (node (ref "R62") (pin "2") (pinfunction "2_2") (pintype "passive"))
    )
    (net (code "65") (name "/DRV56") (class "Default")
      (node (ref "Q27") (pin "1") (pinfunction "G_1") (pintype "passive"))
      (node (ref "R32") (pin "2") (pinfunction "2_2") (pintype "passive"))
    )
    (net (code "66") (name "/DRV57") (class "Default")
      (node (ref "Q46") (pin "1") (pinfunction "G_1") (pintype "passive"))
      (node (ref "R63") (pin "2") (pinfunction "2_2") (pintype "passive"))
    )
    (net (code "67") (name "/DRV58") (class "Default")
      (node (ref "Q47") (pin "1") (pinfunction "G_1") (pintype "passive"))
      (node (ref "R64") (pin "2") (pinfunction "2_2") (pintype "passive"))
    )
    (net (code "68") (name "/DRV59") (class "Default")
      (node (ref "Q48") (pin "1") (pinfunction "G_1") (pintype "passive"))
      (node (ref "R65") (pin "2") (pinfunction "2_2") (pintype "passive"))
    )
    (net (code "69") (name "/DRV60") (class "Default")
      (node (ref "Q49") (pin "1") (pinfunction "G_1") (pintype "passive"))
      (node (ref "R66") (pin "2") (pinfunction "2_2") (pintype "passive"))
    )
    (net (code "70") (name "/DRV61") (class "Default")
      (node (ref "Q50") (pin "1") (pinfunction "G_1") (pintype "passive"))
      (node (ref "R67") (pin "2") (pinfunction "2_2") (pintype "passive"))
    )
    (net (code "71") (name "/DRV62") (class "Default")
      (node (ref "Q51") (pin "1") (pinfunction "G_1") (pintype "passive"))
      (node (ref "R68") (pin "2") (pinfunction "2_2") (pintype "passive"))
    )
    (net (code "72") (name "/DRV63") (class "Default")
      (node (ref "Q52") (pin "1") (pinfunction "G_1") (pintype "passive"))
      (node (ref "R69") (pin "2") (pinfunction "2_2") (pintype "passive"))
    )
    (net (code "73") (name "/DRV64") (class "Default")
      (node (ref "Q53") (pin "1") (pinfunction "G_1") (pintype "passive"))
      (node (ref "R70") (pin "2") (pinfunction "2_2") (pintype "passive"))
    )
    (net (code "74") (name "/DRV65") (class "Default")
      (node (ref "Q54") (pin "1") (pinfunction "G_1") (pintype "passive"))
      (node (ref "R71") (pin "2") (pinfunction "2_2") (pintype "passive"))
    )
    (net (code "75") (name "/DRV66") (class "Default")
      (node (ref "Q55") (pin "1") (pinfunction "G_1") (pintype "passive"))
      (node (ref "R72") (pin "2") (pinfunction "2_2") (pintype "passive"))
    )
    (net (code "76") (name "/DRV67") (class "Default")
      (node (ref "Q56") (pin "1") (pinfunction "G_1") (pintype "passive"))
      (node (ref "R73") (pin "2") (pinfunction "2_2") (pintype "passive"))
    )
    (net (code "77") (name "/DRV68") (class "Default")
      (node (ref "Q57") (pin "1") (pinfunction "G_1") (pintype "passive"))
      (node (ref "R74") (pin "2") (pinfunction "2_2") (pintype "passive"))
    )
    (net (code "78") (name "/DRV69") (class "Default")
      (node (ref "Q58") (pin "1") (pinfunction "G_1") (pintype "passive"))
      (node (ref "R75") (pin "2") (pinfunction "2_2") (pintype "passive"))
    )
    (net (code "79") (name "/DRV70") (class "Default")
      (node (ref "Q59") (pin "1") (pinfunction "G_1") (pintype "passive"))
      (node (ref "R76") (pin "2") (pinfunction "2_2") (pintype "passive"))
    )
    (net (code "80") (name "/DRV71") (class "Default")
      (node (ref "Q60") (pin "1") (pinfunction "G_1") (pintype "passive"))
      (node (ref "R77") (pin "2") (pinfunction "2_2") (pintype "passive"))
    )
    (net (code "81") (name "/DRV72") (class "Default")
      (node (ref "Q61") (pin "1") (pinfunction "G_1") (pintype "passive"))
      (node (ref "R78") (pin "2") (pinfunction "2_2") (pintype "passive"))
    )
    (net (code "82") (name "/DRV73") (class "Default")
      (node (ref "Q62") (pin "1") (pinfunction "G_1") (pintype "passive"))
      (node (ref "R79") (pin "2") (pinfunction "2_2") (pintype "passive"))
    )
    (net (code "83") (name "/DRV74") (class "Default")
      (node (ref "Q63") (pin "1") (pinfunction "G_1") (pintype "passive"))
      (node (ref "R80") (pin "2") (pinfunction "2_2") (pintype "passive"))
    )
    (net (code "84") (name "/DRV75") (class "Default")
      (node (ref "Q64") (pin "1") (pinfunction "G_1") (pintype "passive"))
      (node (ref "R81") (pin "2") (pinfunction "2_2") (pintype "passive"))
    )
    (net (code "85") (name "/DRV76") (class "Default")
      (node (ref "Q65") (pin "1") (pinfunction "G_1") (pintype "passive"))
      (node (ref "R82") (pin "2") (pinfunction "2_2") (pintype "passive"))
    )
    (net (code "86") (name "/DRV77") (class "Default")
      (node (ref "Q66") (pin "1") (pinfunction "G_1") (pintype "passive"))
      (node (ref "R83") (pin "2") (pinfunction "2_2") (pintype "passive"))
    )
    (net (code "87") (name "/DRV78") (class "Default")
      (node (ref "Q67") (pin "1") (pinfunction "G_1") (pintype "passive"))
      (node (ref "R84") (pin "2") (pinfunction "2_2") (pintype "passive"))
    )
    (net (code "88") (name "/DRV79") (class "Default")
      (node (ref "Q68") (pin "1") (pinfunction "G_1") (pintype "passive"))
      (node (ref "R85") (pin "2") (pinfunction "2_2") (pintype "passive"))
    )
    (net (code "89") (name "/DRV80") (class "Default")
      (node (ref "Q69") (pin "1") (pinfunction "G_1") (pintype "passive"))
      (node (ref "R86") (pin "2") (pinfunction "2_2") (pintype "passive"))
    )
    (net (code "90") (name "/DRV81") (class "Default")
      (node (ref "Q70") (pin "1") (pinfunction "G_1") (pintype "passive"))
      (node (ref "R87") (pin "2") (pinfunction "2_2") (pintype "passive"))
    )
    (net (code "91") (name "/DRV82") (class "Default")
      (node (ref "Q71") (pin "1") (pinfunction "G_1") (pintype "passive"))
      (node (ref "R88") (pin "2") (pinfunction "2_2") (pintype "passive"))
    )
    (net (code "92") (name "/DRV83") (class "Default")
      (node (ref "Q72") (pin "1") (pinfunction "G_1") (pintype "passive"))
      (node (ref "R89") (pin "2") (pinfunction "2_2") (pintype "passive"))
    )
    (net (code "93") (name "/DRV84") (class "Default")
      (node (ref "Q73") (pin "1") (pinfunction "G_1") (pintype "passive"))
      (node (ref "R90") (pin "2") (pinfunction "2_2") (pintype "passive"))
    )
    (net (code "94") (name "/DRV85") (class "Default")
      (node (ref "Q74") (pin "1") (pinfunction "G_1") (pintype "passive"))
      (node (ref "R91") (pin "2") (pinfunction "2_2") (pintype "passive"))
    )
    (net (code "95") (name "/DRV86") (class "Default")
      (node (ref "Q75") (pin "1") (pinfunction "G_1") (pintype "passive"))
      (node (ref "R92") (pin "2") (pinfunction "2_2") (pintype "passive"))
    )
    (net (code "96") (name "/DRV87") (class "Default")
      (node (ref "Q76") (pin "1") (pinfunction "G_1") (pintype "passive"))
      (node (ref "R93") (pin "2") (pinfunction "2_2") (pintype "passive"))
    )
    (net (code "97") (name "/DRV88") (class "Default")
      (node (ref "Q81") (pin "1") (pinfunction "G_1") (pintype "passive"))
      (node (ref "R143") (pin "2") (pinfunction "2_2") (pintype "passive"))
    )
    (net (code "98") (name "/DRV89") (class "Default")
      (node (ref "Q82") (pin "1") (pinfunction "G_1") (pintype "passive"))
      (node (ref "R144") (pin "2") (pinfunction "2_2") (pintype "passive"))
    )
    (net (code "99") (name "/DRV90") (class "Default")
      (node (ref "Q83") (pin "1") (pinfunction "G_1") (pintype "passive"))
      (node (ref "R145") (pin "2") (pinfunction "2_2") (pintype "passive"))
    )
    (net (code "100") (name "/DRV91") (class "Default")
      (node (ref "Q84") (pin "1") (pinfunction "G_1") (pintype "passive"))
      (node (ref "R146") (pin "2") (pinfunction "2_2") (pintype "passive"))
    )
    (net (code "101") (name "/DRV92") (class "Default")
      (node (ref "Q85") (pin "1") (pinfunction "G_1") (pintype "passive"))
      (node (ref "R147") (pin "2") (pinfunction "2_2") (pintype "passive"))
    )
    (net (code "102") (name "/DRV93") (class "Default")
      (node (ref "Q86") (pin "1") (pinfunction "G_1") (pintype "passive"))
      (node (ref "R148") (pin "2") (pinfunction "2_2") (pintype "passive"))
    )
    (net (code "103") (name "/DRV94") (class "Default")
      (node (ref "Q87") (pin "1") (pinfunction "G_1") (pintype "passive"))
      (node (ref "R149") (pin "2") (pinfunction "2_2") (pintype "passive"))
    )
    (net (code "104") (name "/DRV95") (class "Default")
      (node (ref "Q88") (pin "1") (pinfunction "G_1") (pintype "passive"))
      (node (ref "R150") (pin "2") (pinfunction "2_2") (pintype "passive"))
    )
    (net (code "105") (name "/DRV96") (class "Default")
      (node (ref "Q89") (pin "1") (pinfunction "G_1") (pintype "passive"))
      (node (ref "R151") (pin "2") (pinfunction "2_2") (pintype "passive"))
    )
    (net (code "106") (name "/DRV97") (class "Default")
      (node (ref "Q90") (pin "1") (pinfunction "G_1") (pintype "passive"))
      (node (ref "R152") (pin "2") (pinfunction "2_2") (pintype "passive"))
    )
    (net (code "107") (name "/DRV98") (class "Default")
      (node (ref "Q91") (pin "1") (pinfunction "G_1") (pintype "passive"))
      (node (ref "R153") (pin "2") (pinfunction "2_2") (pintype "passive"))
    )
    (net (code "108") (name "/DRV99") (class "Default")
      (node (ref "Q92") (pin "1") (pinfunction "G_1") (pintype "passive"))
      (node (ref "R154") (pin "2") (pinfunction "2_2") (pintype "passive"))
    )
    (net (code "109") (name "/DRV100") (class "Default")
      (node (ref "Q93") (pin "1") (pinfunction "G_1") (pintype "passive"))
      (node (ref "R155") (pin "2") (pinfunction "2_2") (pintype "passive"))
    )
    (net (code "110") (name "/DRV101") (class "Default")
      (node (ref "Q94") (pin "1") (pinfunction "G_1") (pintype "passive"))
      (node (ref "R156") (pin "2") (pinfunction "2_2") (pintype "passive"))
    )
    (net (code "111") (name "/DRV102") (class "Default")
      (node (ref "Q95") (pin "1") (pinfunction "G_1") (pintype "passive"))
      (node (ref "R157") (pin "2") (pinfunction "2_2") (pintype "passive"))
    )
    (net (code "112") (name "/DRV103") (class "Default")
      (node (ref "Q96") (pin "1") (pinfunction "G_1") (pintype "passive"))
      (node (ref "R158") (pin "2") (pinfunction "2_2") (pintype "passive"))
    )
    (net (code "114") (name "5V0R") (class "Default")
      (node (ref "K28") (pin "1") (pinfunction "+_1") (pintype "passive"))
      (node (ref "K29") (pin "1") (pinfunction "+_1") (pintype "passive"))
      (node (ref "K30") (pin "1") (pinfunction "+_1") (pintype "passive"))
      (node (ref "K31") (pin "1") (pinfunction "+_1") (pintype "passive"))
      (node (ref "K32") (pin "1") (pinfunction "+_1") (pintype "passive"))
      (node (ref "K33") (pin "1") (pinfunction "+_1") (pintype "passive"))
      (node (ref "K34") (pin "1") (pinfunction "+_1") (pintype "passive"))
      (node (ref "K35") (pin "1") (pinfunction "+_1") (pintype "passive"))
      (node (ref "K36") (pin "1") (pinfunction "+_1") (pintype "passive"))
      (node (ref "K37") (pin "1") (pinfunction "+_1") (pintype "passive"))
      (node (ref "K38") (pin "1") (pinfunction "+_1") (pintype "passive"))
      (node (ref "K39") (pin "1") (pinfunction "+_1") (pintype "passive"))
      (node (ref "K40") (pin "1") (pinfunction "+_1") (pintype "passive"))
      (node (ref "K41") (pin "1") (pinfunction "+_1") (pintype "passive"))
      (node (ref "K42") (pin "1") (pinfunction "+_1") (pintype "passive"))
      (node (ref "K43") (pin "1") (pinfunction "+_1") (pintype "passive"))
      (node (ref "K44") (pin "1") (pinfunction "+_1") (pintype "passive"))
      (node (ref "K45") (pin "1") (pinfunction "+_1") (pintype "passive"))
      (node (ref "K46") (pin "1") (pinfunction "+_1") (pintype "passive"))
      (node (ref "K47") (pin "1") (pinfunction "+_1") (pintype "passive"))
      (node (ref "K48") (pin "1") (pinfunction "+_1") (pintype "passive"))
      (node (ref "K49") (pin "1") (pinfunction "+_1") (pintype "passive"))
      (node (ref "K50") (pin "1") (pinfunction "+_1") (pintype "passive"))
      (node (ref "K51") (pin "1") (pinfunction "+_1") (pintype "passive"))
      (node (ref "K52") (pin "1") (pinfunction "+_1") (pintype "passive"))
      (node (ref "K53") (pin "1") (pinfunction "+_1") (pintype "passive"))
      (node (ref "K54") (pin "1") (pinfunction "+_1") (pintype "passive"))
      (node (ref "K55") (pin "1") (pinfunction "+_1") (pintype "passive"))
      (node (ref "K56") (pin "1") (pinfunction "+_1") (pintype "passive"))
      (node (ref "K57") (pin "1") (pinfunction "+_1") (pintype "passive"))
      (node (ref "K58") (pin "1") (pinfunction "+_1") (pintype "passive"))
      (node (ref "K59") (pin "1") (pinfunction "+_1") (pintype "passive"))
      (node (ref "K60") (pin "1") (pinfunction "+_1") (pintype "passive"))
      (node (ref "K61") (pin "1") (pinfunction "+_1") (pintype "passive"))
      (node (ref "K62") (pin "1") (pinfunction "+_1") (pintype "passive"))
      (node (ref "K63") (pin "1") (pinfunction "+_1") (pintype "passive"))
      (node (ref "K64") (pin "1") (pinfunction "+_1") (pintype "passive"))
      (node (ref "K65") (pin "1") (pinfunction "+_1") (pintype "passive"))
      (node (ref "K66") (pin "1") (pinfunction "+_1") (pintype "passive"))
      (node (ref "K67") (pin "1") (pinfunction "+_1") (pintype "passive"))
      (node (ref "K68") (pin "1") (pinfunction "+_1") (pintype "passive"))
      (node (ref "K69") (pin "1") (pinfunction "+_1") (pintype "passive"))
      (node (ref "K70") (pin "1") (pinfunction "+_1") (pintype "passive"))
      (node (ref "K71") (pin "1") (pinfunction "+_1") (pintype "passive"))
      (node (ref "K72") (pin "1") (pinfunction "+_1") (pintype "passive"))
      (node (ref "K73") (pin "1") (pinfunction "+_1") (pintype "passive"))
      (node (ref "K74") (pin "1") (pinfunction "+_1") (pintype "passive"))
      (node (ref "K75") (pin "1") (pinfunction "+_1") (pintype "passive"))
      (node (ref "K76") (pin "1") (pinfunction "+_1") (pintype "passive"))
      (node (ref "K77") (pin "1") (pinfunction "+_1") (pintype "passive"))
      (node (ref "K78") (pin "1") (pinfunction "+_1") (pintype "passive"))
      (node (ref "K79") (pin "1") (pinfunction "+_1") (pintype "passive"))
      (node (ref "K80") (pin "1") (pinfunction "+_1") (pintype "passive"))
      (node (ref "K81") (pin "1") (pinfunction "+_1") (pintype "passive"))
      (node (ref "K82") (pin "1") (pinfunction "+_1") (pintype "passive"))
      (node (ref "K83") (pin "1") (pinfunction "+_1") (pintype "passive"))
      (node (ref "K84") (pin "1") (pinfunction "+_1") (pintype "passive"))
      (node (ref "K85") (pin "1") (pinfunction "+_1") (pintype "passive"))
      (node (ref "K86") (pin "1") (pinfunction "+_1") (pintype "passive"))
      (node (ref "K87") (pin "1") (pinfunction "+_1") (pintype "passive"))
      (node (ref "K88") (pin "1") (pinfunction "+_1") (pintype "passive"))
      (node (ref "K89") (pin "1") (pinfunction "+_1") (pintype "passive"))
      (node (ref "K90") (pin "1") (pinfunction "+_1") (pintype "passive"))
      (node (ref "K91") (pin "1") (pinfunction "+_1") (pintype "passive"))
    )
    (net (code "115") (name "GND") (class "Default")
      (node (ref "Q27") (pin "2") (pinfunction "S_2") (pintype "passive"))
      (node (ref "Q28") (pin "2") (pinfunction "S_2") (pintype "passive"))
      (node (ref "Q31") (pin "2") (pinfunction "S_2") (pintype "passive"))
      (node (ref "Q32") (pin "2") (pinfunction "S_2") (pintype "passive"))
      (node (ref "Q33") (pin "2") (pinfunction "S_2") (pintype "passive"))
      (node (ref "Q34") (pin "2") (pinfunction "S_2") (pintype "passive"))
      (node (ref "Q35") (pin "2") (pinfunction "S_2") (pintype "passive"))
      (node (ref "Q36") (pin "2") (pinfunction "S_2") (pintype "passive"))
      (node (ref "Q37") (pin "2") (pinfunction "S_2") (pintype "passive"))
      (node (ref "Q38") (pin "2") (pinfunction "S_2") (pintype "passive"))
      (node (ref "Q39") (pin "2") (pinfunction "S_2") (pintype "passive"))
      (node (ref "Q40") (pin "2") (pinfunction "S_2") (pintype "passive"))
      (node (ref "Q41") (pin "2") (pinfunction "S_2") (pintype "passive"))
      (node (ref "Q42") (pin "2") (pinfunction "S_2") (pintype "passive"))
      (node (ref "Q43") (pin "2") (pinfunction "S_2") (pintype "passive"))
      (node (ref "Q44") (pin "2") (pinfunction "S_2") (pintype "passive"))
      (node (ref "Q45") (pin "2") (pinfunction "S_2") (pintype "passive"))
      (node (ref "Q46") (pin "2") (pinfunction "S_2") (pintype "passive"))
      (node (ref "Q47") (pin "2") (pinfunction "S_2") (pintype "passive"))
      (node (ref "Q48") (pin "2") (pinfunction "S_2") (pintype "passive"))
      (node (ref "Q49") (pin "2") (pinfunction "S_2") (pintype "passive"))
      (node (ref "Q50") (pin "2") (pinfunction "S_2") (pintype "passive"))
      (node (ref "Q51") (pin "2") (pinfunction "S_2") (pintype "passive"))
      (node (ref "Q52") (pin "2") (pinfunction "S_2") (pintype "passive"))
      (node (ref "Q53") (pin "2") (pinfunction "S_2") (pintype "passive"))
      (node (ref "Q54") (pin "2") (pinfunction "S_2") (pintype "passive"))
      (node (ref "Q55") (pin "2") (pinfunction "S_2") (pintype "passive"))
      (node (ref "Q56") (pin "2") (pinfunction "S_2") (pintype "passive"))
      (node (ref "Q57") (pin "2") (pinfunction "S_2") (pintype "passive"))
      (node (ref "Q58") (pin "2") (pinfunction "S_2") (pintype "passive"))
      (node (ref "Q59") (pin "2") (pinfunction "S_2") (pintype "passive"))
      (node (ref "Q60") (pin "2") (pinfunction "S_2") (pintype "passive"))
      (node (ref "Q61") (pin "2") (pinfunction "S_2") (pintype "passive"))
      (node (ref "Q62") (pin "2") (pinfunction "S_2") (pintype "passive"))
      (node (ref "Q63") (pin "2") (pinfunction "S_2") (pintype "passive"))
      (node (ref "Q64") (pin "2") (pinfunction "S_2") (pintype "passive"))
      (node (ref "Q65") (pin "2") (pinfunction "S_2") (pintype "passive"))
      (node (ref "Q66") (pin "2") (pinfunction "S_2") (pintype "passive"))
      (node (ref "Q67") (pin "2") (pinfunction "S_2") (pintype "passive"))
      (node (ref "Q68") (pin "2") (pinfunction "S_2") (pintype "passive"))
      (node (ref "Q69") (pin "2") (pinfunction "S_2") (pintype "passive"))
      (node (ref "Q70") (pin "2") (pinfunction "S_2") (pintype "passive"))
      (node (ref "Q71") (pin "2") (pinfunction "S_2") (pintype "passive"))
      (node (ref "Q72") (pin "2") (pinfunction "S_2") (pintype "passive"))
      (node (ref "Q73") (pin "2") (pinfunction "S_2") (pintype "passive"))
      (node (ref "Q74") (pin "2") (pinfunction "S_2") (pintype "passive"))
      (node (ref "Q75") (pin "2") (pinfunction "S_2") (pintype "passive"))
      (node (ref "Q76") (pin "2") (pinfunction "S_2") (pintype "passive"))
      (node (ref "Q81") (pin "2") (pinfunction "S_2") (pintype "passive"))
      (node (ref "Q82") (pin "2") (pinfunction "S_2") (pintype "passive"))
      (node (ref "Q83") (pin "2") (pinfunction "S_2") (pintype "passive"))
      (node (ref "Q84") (pin "2") (pinfunction "S_2") (pintype "passive"))
      (node (ref "Q85") (pin "2") (pinfunction "S_2") (pintype "passive"))
      (node (ref "Q86") (pin "2") (pinfunction "S_2") (pintype "passive"))
      (node (ref "Q87") (pin "2") (pinfunction "S_2") (pintype "passive"))
      (node (ref "Q88") (pin "2") (pinfunction "S_2") (pintype "passive"))
      (node (ref "Q89") (pin "2") (pinfunction "S_2") (pintype "passive"))
      (node (ref "Q90") (pin "2") (pinfunction "S_2") (pintype "passive"))
      (node (ref "Q91") (pin "2") (pinfunction "S_2") (pintype "passive"))
      (node (ref "Q92") (pin "2") (pinfunction "S_2") (pintype "passive"))
      (node (ref "Q93") (pin "2") (pinfunction "S_2") (pintype "passive"))
      (node (ref "Q94") (pin "2") (pinfunction "S_2") (pintype "passive"))
      (node (ref "Q95") (pin "2") (pinfunction "S_2") (pintype "passive"))
      (node (ref "Q96") (pin "2") (pinfunction "S_2") (pintype "passive"))
      (node (ref "R143") (pin "1") (pinfunction "1_1") (pintype "passive"))
      (node (ref "R144") (pin "1") (pinfunction "1_1") (pintype "passive"))
      (node (ref "R145") (pin "1") (pinfunction "1_1") (pintype "passive"))
      (node (ref "R146") (pin "1") (pinfunction "1_1") (pintype "passive"))
      (node (ref "R147") (pin "1") (pinfunction "1_1") (pintype "passive"))
      (node (ref "R148") (pin "1") (pinfunction "1_1") (pintype "passive"))
      (node (ref "R149") (pin "1") (pinfunction "1_1") (pintype "passive"))
      (node (ref "R150") (pin "1") (pinfunction "1_1") (pintype "passive"))
      (node (ref "R151") (pin "1") (pinfunction "1_1") (pintype "passive"))
      (node (ref "R152") (pin "1") (pinfunction "1_1") (pintype "passive"))
      (node (ref "R153") (pin "1") (pinfunction "1_1") (pintype "passive"))
      (node (ref "R154") (pin "1") (pinfunction "1_1") (pintype "passive"))
      (node (ref "R155") (pin "1") (pinfunction "1_1") (pintype "passive"))
      (node (ref "R156") (pin "1") (pinfunction "1_1") (pintype "passive"))
      (node (ref "R157") (pin "1") (pinfunction "1_1") (pintype "passive"))
      (node (ref "R158") (pin "1") (pinfunction "1_1") (pintype "passive"))
      (node (ref "R32") (pin "1") (pinfunction "1_1") (pintype "passive"))
      (node (ref "R33") (pin "1") (pinfunction "1_1") (pintype "passive"))
      (node (ref "R48") (pin "1") (pinfunction "1_1") (pintype "passive"))
      (node (ref "R49") (pin "1") (pinfunction "1_1") (pintype "passive"))
      (node (ref "R50") (pin "1") (pinfunction "1_1") (pintype "passive"))
      (node (ref "R51") (pin "1") (pinfunction "1_1") (pintype "passive"))
      (node (ref "R52") (pin "1") (pinfunction "1_1") (pintype "passive"))
      (node (ref "R53") (pin "1") (pinfunction "1_1") (pintype "passive"))
      (node (ref "R54") (pin "1") (pinfunction "1_1") (pintype "passive"))
      (node (ref "R55") (pin "1") (pinfunction "1_1") (pintype "passive"))
      (node (ref "R56") (pin "1") (pinfunction "1_1") (pintype "passive"))
      (node (ref "R57") (pin "1") (pinfunction "1_1") (pintype "passive"))
      (node (ref "R58") (pin "1") (pinfunction "1_1") (pintype "passive"))
      (node (ref "R59") (pin "1") (pinfunction "1_1") (pintype "passive"))
      (node (ref "R60") (pin "1") (pinfunction "1_1") (pintype "passive"))
      (node (ref "R61") (pin "1") (pinfunction "1_1") (pintype "passive"))
      (node (ref "R62") (pin "1") (pinfunction "1_1") (pintype "passive"))
      (node (ref "R63") (pin "1") (pinfunction "1_1") (pintype "passive"))
      (node (ref "R64") (pin "1") (pinfunction "1_1") (pintype "passive"))
      (node (ref "R65") (pin "1") (pinfunction "1_1") (pintype "passive"))
      (node (ref "R66") (pin "1") (pinfunction "1_1") (pintype "passive"))
      (node (ref "R67") (pin "1") (pinfunction "1_1") (pintype "passive"))
      (node (ref "R68") (pin "1") (pinfunction "1_1") (pintype "passive"))
      (node (ref "R69") (pin "1") (pinfunction "1_1") (pintype "passive"))
      (node (ref "R70") (pin "1") (pinfunction "1_1") (pintype "passive"))
      (node (ref "R71") (pin "1") (pinfunction "1_1") (pintype "passive"))
      (node (ref "R72") (pin "1") (pinfunction "1_1") (pintype "passive"))
      (node (ref "R73") (pin "1") (pinfunction "1_1") (pintype "passive"))
      (node (ref "R74") (pin "1") (pinfunction "1_1") (pintype "passive"))
      (node (ref "R75") (pin "1") (pinfunction "1_1") (pintype "passive"))
      (node (ref "R76") (pin "1") (pinfunction "1_1") (pintype "passive"))
      (node (ref "R77") (pin "1") (pinfunction "1_1") (pintype "passive"))
      (node (ref "R78") (pin "1") (pinfunction "1_1") (pintype "passive"))
      (node (ref "R79") (pin "1") (pinfunction "1_1") (pintype "passive"))
      (node (ref "R80") (pin "1") (pinfunction "1_1") (pintype "passive"))
      (node (ref "R81") (pin "1") (pinfunction "1_1") (pintype "passive"))
      (node (ref "R82") (pin "1") (pinfunction "1_1") (pintype "passive"))
      (node (ref "R83") (pin "1") (pinfunction "1_1") (pintype "passive"))
      (node (ref "R84") (pin "1") (pinfunction "1_1") (pintype "passive"))
      (node (ref "R85") (pin "1") (pinfunction "1_1") (pintype "passive"))
      (node (ref "R86") (pin "1") (pinfunction "1_1") (pintype "passive"))
      (node (ref "R87") (pin "1") (pinfunction "1_1") (pintype "passive"))
      (node (ref "R88") (pin "1") (pinfunction "1_1") (pintype "passive"))
      (node (ref "R89") (pin "1") (pinfunction "1_1") (pintype "passive"))
      (node (ref "R90") (pin "1") (pinfunction "1_1") (pintype "passive"))
      (node (ref "R91") (pin "1") (pinfunction "1_1") (pintype "passive"))
      (node (ref "R92") (pin "1") (pinfunction "1_1") (pintype "passive"))
      (node (ref "R93") (pin "1") (pinfunction "1_1") (pintype "passive"))
    )
    (net (code "116") (name "Net-(K28A-CA)") (class "Default")
      (node (ref "K28") (pin "3") (pinfunction "CA_3") (pintype "passive"))
      (node (ref "X30") (pin "1") (pinfunction "1_1") (pintype "passive"))
    )
    (net (code "117") (name "Net-(K28A-CB)") (class "Default")
      (node (ref "K28") (pin "4") (pinfunction "CB_4") (pintype "passive"))
      (node (ref "X28") (pin "1") (pinfunction "1_1") (pintype "passive"))
    )
    (net (code "118") (name "Net-(K28B--)") (class "Default")
      (node (ref "K28") (pin "2") (pinfunction "-_2") (pintype "passive"))
      (node (ref "Q28") (pin "3") (pinfunction "D_3") (pintype "passive"))
    )
    (net (code "119") (name "Net-(K29A-CA)") (class "Default")
      (node (ref "K29") (pin "3") (pinfunction "CA_3") (pintype "passive"))
      (node (ref "X30") (pin "2") (pinfunction "2_2") (pintype "passive"))
    )
    (net (code "120") (name "Net-(K29A-CB)") (class "Default")
      (node (ref "K29") (pin "4") (pinfunction "CB_4") (pintype "passive"))
      (node (ref "X28") (pin "2") (pinfunction "2_2") (pintype "passive"))
    )
    (net (code "121") (name "Net-(K29B--)") (class "Default")
      (node (ref "K29") (pin "2") (pinfunction "-_2") (pintype "passive"))
      (node (ref "Q31") (pin "3") (pinfunction "D_3") (pintype "passive"))
    )
    (net (code "122") (name "Net-(K30A-CA)") (class "Default")
      (node (ref "K30") (pin "3") (pinfunction "CA_3") (pintype "passive"))
      (node (ref "X30") (pin "3") (pinfunction "3_3") (pintype "passive"))
    )
    (net (code "123") (name "Net-(K30A-CB)") (class "Default")
      (node (ref "K30") (pin "4") (pinfunction "CB_4") (pintype "passive"))
      (node (ref "X28") (pin "3") (pinfunction "3_3") (pintype "passive"))
    )
    (net (code "124") (name "Net-(K30B--)") (class "Default")
      (node (ref "K30") (pin "2") (pinfunction "-_2") (pintype "passive"))
      (node (ref "Q32") (pin "3") (pinfunction "D_3") (pintype "passive"))
    )
    (net (code "125") (name "Net-(K31A-CA)") (class "Default")
      (node (ref "K31") (pin "3") (pinfunction "CA_3") (pintype "passive"))
      (node (ref "X30") (pin "4") (pinfunction "4_4") (pintype "passive"))
    )
    (net (code "126") (name "Net-(K31A-CB)") (class "Default")
      (node (ref "K31") (pin "4") (pinfunction "CB_4") (pintype "passive"))
      (node (ref "X28") (pin "4") (pinfunction "4_4") (pintype "passive"))
    )
    (net (code "127") (name "Net-(K31B--)") (class "Default")
      (node (ref "K31") (pin "2") (pinfunction "-_2") (pintype "passive"))
      (node (ref "Q33") (pin "3") (pinfunction "D_3") (pintype "passive"))
    )
    (net (code "128") (name "Net-(K32A-CA)") (class "Default")
      (node (ref "K32") (pin "3") (pinfunction "CA_3") (pintype "passive"))
      (node (ref "X30") (pin "5") (pinfunction "5_5") (pintype "passive"))
    )
    (net (code "129") (name "Net-(K32A-CB)") (class "Default")
      (node (ref "K32") (pin "4") (pinfunction "CB_4") (pintype "passive"))
      (node (ref "X28") (pin "5") (pinfunction "5_5") (pintype "passive"))
    )
    (net (code "130") (name "Net-(K32B--)") (class "Default")
      (node (ref "K32") (pin "2") (pinfunction "-_2") (pintype "passive"))
      (node (ref "Q34") (pin "3") (pinfunction "D_3") (pintype "passive"))
    )
    (net (code "131") (name "Net-(K33A-CA)") (class "Default")
      (node (ref "K33") (pin "3") (pinfunction "CA_3") (pintype "passive"))
      (node (ref "X30") (pin "6") (pinfunction "6_6") (pintype "passive"))
    )
    (net (code "132") (name "Net-(K33A-CB)") (class "Default")
      (node (ref "K33") (pin "4") (pinfunction "CB_4") (pintype "passive"))
      (node (ref "X28") (pin "6") (pinfunction "6_6") (pintype "passive"))
    )
    (net (code "133") (name "Net-(K33B--)") (class "Default")
      (node (ref "K33") (pin "2") (pinfunction "-_2") (pintype "passive"))
      (node (ref "Q35") (pin "3") (pinfunction "D_3") (pintype "passive"))
    )
    (net (code "134") (name "Net-(K34A-CA)") (class "Default")
      (node (ref "K34") (pin "3") (pinfunction "CA_3") (pintype "passive"))
      (node (ref "X30") (pin "7") (pinfunction "7_7") (pintype "passive"))
    )
    (net (code "135") (name "Net-(K34A-CB)") (class "Default")
      (node (ref "K34") (pin "4") (pinfunction "CB_4") (pintype "passive"))
      (node (ref "X28") (pin "7") (pinfunction "7_7") (pintype "passive"))
    )
    (net (code "136") (name "Net-(K34B--)") (class "Default")
      (node (ref "K34") (pin "2") (pinfunction "-_2") (pintype "passive"))
      (node (ref "Q36") (pin "3") (pinfunction "D_3") (pintype "passive"))
    )
    (net (code "137") (name "Net-(K35A-CA)") (class "Default")
      (node (ref "K35") (pin "3") (pinfunction "CA_3") (pintype "passive"))
      (node (ref "X30") (pin "8") (pinfunction "8_8") (pintype "passive"))
    )
    (net (code "138") (name "Net-(K35A-CB)") (class "Default")
      (node (ref "K35") (pin "4") (pinfunction "CB_4") (pintype "passive"))
      (node (ref "X28") (pin "8") (pinfunction "8_8") (pintype "passive"))
    )
    (net (code "139") (name "Net-(K35B--)") (class "Default")
      (node (ref "K35") (pin "2") (pinfunction "-_2") (pintype "passive"))
      (node (ref "Q37") (pin "3") (pinfunction "D_3") (pintype "passive"))
    )
    (net (code "140") (name "Net-(K36A-CA)") (class "Default")
      (node (ref "K36") (pin "3") (pinfunction "CA_3") (pintype "passive"))
      (node (ref "X30") (pin "9") (pinfunction "9_9") (pintype "passive"))
    )
    (net (code "141") (name "Net-(K36A-CB)") (class "Default")
      (node (ref "K36") (pin "4") (pinfunction "CB_4") (pintype "passive"))
      (node (ref "X28") (pin "9") (pinfunction "9_9") (pintype "passive"))
    )
    (net (code "142") (name "Net-(K36B--)") (class "Default")
      (node (ref "K36") (pin "2") (pinfunction "-_2") (pintype "passive"))
      (node (ref "Q38") (pin "3") (pinfunction "D_3") (pintype "passive"))
    )
    (net (code "143") (name "Net-(K37A-CA)") (class "Default")
      (node (ref "K37") (pin "3") (pinfunction "CA_3") (pintype "passive"))
      (node (ref "X30") (pin "10") (pinfunction "10_10") (pintype "passive"))
    )
    (net (code "144") (name "Net-(K37A-CB)") (class "Default")
      (node (ref "K37") (pin "4") (pinfunction "CB_4") (pintype "passive"))
      (node (ref "X28") (pin "10") (pinfunction "10_10") (pintype "passive"))
    )
    (net (code "145") (name "Net-(K37B--)") (class "Default")
      (node (ref "K37") (pin "2") (pinfunction "-_2") (pintype "passive"))
      (node (ref "Q39") (pin "3") (pinfunction "D_3") (pintype "passive"))
    )
    (net (code "146") (name "Net-(K38A-CA)") (class "Default")
      (node (ref "K38") (pin "3") (pinfunction "CA_3") (pintype "passive"))
      (node (ref "X30") (pin "11") (pinfunction "11_11") (pintype "passive"))
    )
    (net (code "147") (name "Net-(K38A-CB)") (class "Default")
      (node (ref "K38") (pin "4") (pinfunction "CB_4") (pintype "passive"))
      (node (ref "X28") (pin "11") (pinfunction "11_11") (pintype "passive"))
    )
    (net (code "148") (name "Net-(K38B--)") (class "Default")
      (node (ref "K38") (pin "2") (pinfunction "-_2") (pintype "passive"))
      (node (ref "Q40") (pin "3") (pinfunction "D_3") (pintype "passive"))
    )
    (net (code "149") (name "Net-(K39A-CA)") (class "Default")
      (node (ref "K39") (pin "3") (pinfunction "CA_3") (pintype "passive"))
      (node (ref "X30") (pin "12") (pinfunction "12_12") (pintype "passive"))
    )
    (net (code "150") (name "Net-(K39A-CB)") (class "Default")
      (node (ref "K39") (pin "4") (pinfunction "CB_4") (pintype "passive"))
      (node (ref "X28") (pin "12") (pinfunction "12_12") (pintype "passive"))
    )
    (net (code "151") (name "Net-(K39B--)") (class "Default")
      (node (ref "K39") (pin "2") (pinfunction "-_2") (pintype "passive"))
      (node (ref "Q41") (pin "3") (pinfunction "D_3") (pintype "passive"))
    )
    (net (code "152") (name "Net-(K40A-CA)") (class "Default")
      (node (ref "K40") (pin "3") (pinfunction "CA_3") (pintype "passive"))
      (node (ref "X30") (pin "13") (pinfunction "13_13") (pintype "passive"))
    )
    (net (code "153") (name "Net-(K40A-CB)") (class "Default")
      (node (ref "K40") (pin "4") (pinfunction "CB_4") (pintype "passive"))
      (node (ref "X28") (pin "13") (pinfunction "13_13") (pintype "passive"))
    )
    (net (code "154") (name "Net-(K40B--)") (class "Default")
      (node (ref "K40") (pin "2") (pinfunction "-_2") (pintype "passive"))
      (node (ref "Q42") (pin "3") (pinfunction "D_3") (pintype "passive"))
    )
    (net (code "155") (name "Net-(K41A-CA)") (class "Default")
      (node (ref "K41") (pin "3") (pinfunction "CA_3") (pintype "passive"))
      (node (ref "X30") (pin "14") (pinfunction "14_14") (pintype "passive"))
    )
    (net (code "156") (name "Net-(K41A-CB)") (class "Default")
      (node (ref "K41") (pin "4") (pinfunction "CB_4") (pintype "passive"))
      (node (ref "X28") (pin "14") (pinfunction "14_14") (pintype "passive"))
    )
    (net (code "157") (name "Net-(K41B--)") (class "Default")
      (node (ref "K41") (pin "2") (pinfunction "-_2") (pintype "passive"))
      (node (ref "Q43") (pin "3") (pinfunction "D_3") (pintype "passive"))
    )
    (net (code "158") (name "Net-(K42A-CA)") (class "Default")
      (node (ref "K42") (pin "3") (pinfunction "CA_3") (pintype "passive"))
      (node (ref "X30") (pin "15") (pinfunction "15_15") (pintype "passive"))
    )
    (net (code "159") (name "Net-(K42A-CB)") (class "Default")
      (node (ref "K42") (pin "4") (pinfunction "CB_4") (pintype "passive"))
      (node (ref "X28") (pin "15") (pinfunction "15_15") (pintype "passive"))
    )
    (net (code "160") (name "Net-(K42B--)") (class "Default")
      (node (ref "K42") (pin "2") (pinfunction "-_2") (pintype "passive"))
      (node (ref "Q44") (pin "3") (pinfunction "D_3") (pintype "passive"))
    )
    (net (code "161") (name "Net-(K43A-CA)") (class "Default")
      (node (ref "K43") (pin "3") (pinfunction "CA_3") (pintype "passive"))
      (node (ref "X30") (pin "16") (pinfunction "16_16") (pintype "passive"))
    )
    (net (code "162") (name "Net-(K43A-CB)") (class "Default")
      (node (ref "K43") (pin "4") (pinfunction "CB_4") (pintype "passive"))
      (node (ref "X28") (pin "16") (pinfunction "16_16") (pintype "passive"))
    )
    (net (code "163") (name "Net-(K43B--)") (class "Default")
      (node (ref "K43") (pin "2") (pinfunction "-_2") (pintype "passive"))
      (node (ref "Q45") (pin "3") (pinfunction "D_3") (pintype "passive"))
    )
    (net (code "164") (name "Net-(K44A-CA)") (class "Default")
      (node (ref "K44") (pin "3") (pinfunction "CA_3") (pintype "passive"))
      (node (ref "X30") (pin "17") (pinfunction "17_17") (pintype "passive"))
    )
    (net (code "165") (name "Net-(K44A-CB)") (class "Default")
      (node (ref "K44") (pin "4") (pinfunction "CB_4") (pintype "passive"))
      (node (ref "X28") (pin "17") (pinfunction "17_17") (pintype "passive"))
    )
    (net (code "166") (name "Net-(K44B--)") (class "Default")
      (node (ref "K44") (pin "2") (pinfunction "-_2") (pintype "passive"))
      (node (ref "Q27") (pin "3") (pinfunction "D_3") (pintype "passive"))
    )
    (net (code "167") (name "Net-(K45A-CA)") (class "Default")
      (node (ref "K45") (pin "3") (pinfunction "CA_3") (pintype "passive"))
      (node (ref "X30") (pin "18") (pinfunction "18_18") (pintype "passive"))
    )
    (net (code "168") (name "Net-(K45A-CB)") (class "Default")
      (node (ref "K45") (pin "4") (pinfunction "CB_4") (pintype "passive"))
      (node (ref "X28") (pin "18") (pinfunction "18_18") (pintype "passive"))
    )
    (net (code "169") (name "Net-(K45B--)") (class "Default")
      (node (ref "K45") (pin "2") (pinfunction "-_2") (pintype "passive"))
      (node (ref "Q46") (pin "3") (pinfunction "D_3") (pintype "passive"))
    )
    (net (code "170") (name "Net-(K46A-CA)") (class "Default")
      (node (ref "K46") (pin "3") (pinfunction "CA_3") (pintype "passive"))
      (node (ref "X30") (pin "19") (pinfunction "19_19") (pintype "passive"))
    )
    (net (code "171") (name "Net-(K46A-CB)") (class "Default")
      (node (ref "K46") (pin "4") (pinfunction "CB_4") (pintype "passive"))
      (node (ref "X28") (pin "19") (pinfunction "19_19") (pintype "passive"))
    )
    (net (code "172") (name "Net-(K46B--)") (class "Default")
      (node (ref "K46") (pin "2") (pinfunction "-_2") (pintype "passive"))
      (node (ref "Q47") (pin "3") (pinfunction "D_3") (pintype "passive"))
    )
    (net (code "173") (name "Net-(K47A-CA)") (class "Default")
      (node (ref "K47") (pin "3") (pinfunction "CA_3") (pintype "passive"))
      (node (ref "X30") (pin "20") (pinfunction "20_20") (pintype "passive"))
    )
    (net (code "174") (name "Net-(K47A-CB)") (class "Default")
      (node (ref "K47") (pin "4") (pinfunction "CB_4") (pintype "passive"))
      (node (ref "X28") (pin "20") (pinfunction "20_20") (pintype "passive"))
    )
    (net (code "175") (name "Net-(K47B--)") (class "Default")
      (node (ref "K47") (pin "2") (pinfunction "-_2") (pintype "passive"))
      (node (ref "Q48") (pin "3") (pinfunction "D_3") (pintype "passive"))
    )
    (net (code "176") (name "Net-(K48A-CA)") (class "Default")
      (node (ref "K48") (pin "3") (pinfunction "CA_3") (pintype "passive"))
      (node (ref "X30") (pin "21") (pinfunction "21_21") (pintype "passive"))
    )
    (net (code "177") (name "Net-(K48A-CB)") (class "Default")
      (node (ref "K48") (pin "4") (pinfunction "CB_4") (pintype "passive"))
      (node (ref "X28") (pin "21") (pinfunction "21_21") (pintype "passive"))
    )
    (net (code "178") (name "Net-(K48B--)") (class "Default")
      (node (ref "K48") (pin "2") (pinfunction "-_2") (pintype "passive"))
      (node (ref "Q49") (pin "3") (pinfunction "D_3") (pintype "passive"))
    )
    (net (code "179") (name "Net-(K49A-CA)") (class "Default")
      (node (ref "K49") (pin "3") (pinfunction "CA_3") (pintype "passive"))
      (node (ref "X30") (pin "22") (pinfunction "22_22") (pintype "passive"))
    )
    (net (code "180") (name "Net-(K49A-CB)") (class "Default")
      (node (ref "K49") (pin "4") (pinfunction "CB_4") (pintype "passive"))
      (node (ref "X28") (pin "22") (pinfunction "22_22") (pintype "passive"))
    )
    (net (code "181") (name "Net-(K49B--)") (class "Default")
      (node (ref "K49") (pin "2") (pinfunction "-_2") (pintype "passive"))
      (node (ref "Q50") (pin "3") (pinfunction "D_3") (pintype "passive"))
    )
    (net (code "182") (name "Net-(K50A-CA)") (class "Default")
      (node (ref "K50") (pin "3") (pinfunction "CA_3") (pintype "passive"))
      (node (ref "X30") (pin "23") (pinfunction "23_23") (pintype "passive"))
    )
    (net (code "183") (name "Net-(K50A-CB)") (class "Default")
      (node (ref "K50") (pin "4") (pinfunction "CB_4") (pintype "passive"))
      (node (ref "X28") (pin "23") (pinfunction "23_23") (pintype "passive"))
    )
    (net (code "184") (name "Net-(K50B--)") (class "Default")
      (node (ref "K50") (pin "2") (pinfunction "-_2") (pintype "passive"))
      (node (ref "Q51") (pin "3") (pinfunction "D_3") (pintype "passive"))
    )
    (net (code "185") (name "Net-(K51A-CA)") (class "Default")
      (node (ref "K51") (pin "3") (pinfunction "CA_3") (pintype "passive"))
      (node (ref "X30") (pin "24") (pinfunction "24_24") (pintype "passive"))
    )
    (net (code "186") (name "Net-(K51A-CB)") (class "Default")
      (node (ref "K51") (pin "4") (pinfunction "CB_4") (pintype "passive"))
      (node (ref "X28") (pin "24") (pinfunction "24_24") (pintype "passive"))
    )
    (net (code "187") (name "Net-(K51B--)") (class "Default")
      (node (ref "K51") (pin "2") (pinfunction "-_2") (pintype "passive"))
      (node (ref "Q52") (pin "3") (pinfunction "D_3") (pintype "passive"))
    )
    (net (code "188") (name "Net-(K52A-CA)") (class "Default")
      (node (ref "K52") (pin "3") (pinfunction "CA_3") (pintype "passive"))
      (node (ref "X30") (pin "25") (pinfunction "25_25") (pintype "passive"))
    )
    (net (code "189") (name "Net-(K52A-CB)") (class "Default")
      (node (ref "K52") (pin "4") (pinfunction "CB_4") (pintype "passive"))
      (node (ref "X28") (pin "25") (pinfunction "25_25") (pintype "passive"))
    )
    (net (code "190") (name "Net-(K52B--)") (class "Default")
      (node (ref "K52") (pin "2") (pinfunction "-_2") (pintype "passive"))
      (node (ref "Q53") (pin "3") (pinfunction "D_3") (pintype "passive"))
    )
    (net (code "191") (name "Net-(K53A-CA)") (class "Default")
      (node (ref "K53") (pin "3") (pinfunction "CA_3") (pintype "passive"))
      (node (ref "X30") (pin "26") (pinfunction "26_26") (pintype "passive"))
    )
    (net (code "192") (name "Net-(K53A-CB)") (class "Default")
      (node (ref "K53") (pin "4") (pinfunction "CB_4") (pintype "passive"))
      (node (ref "X28") (pin "26") (pinfunction "26_26") (pintype "passive"))
    )
    (net (code "193") (name "Net-(K53B--)") (class "Default")
      (node (ref "K53") (pin "2") (pinfunction "-_2") (pintype "passive"))
      (node (ref "Q54") (pin "3") (pinfunction "D_3") (pintype "passive"))
    )
    (net (code "194") (name "Net-(K54A-CA)") (class "Default")
      (node (ref "K54") (pin "3") (pinfunction "CA_3") (pintype "passive"))
      (node (ref "X30") (pin "27") (pinfunction "27_27") (pintype "passive"))
    )
    (net (code "195") (name "Net-(K54A-CB)") (class "Default")
      (node (ref "K54") (pin "4") (pinfunction "CB_4") (pintype "passive"))
      (node (ref "X28") (pin "27") (pinfunction "27_27") (pintype "passive"))
    )
    (net (code "196") (name "Net-(K54B--)") (class "Default")
      (node (ref "K54") (pin "2") (pinfunction "-_2") (pintype "passive"))
      (node (ref "Q55") (pin "3") (pinfunction "D_3") (pintype "passive"))
    )
    (net (code "197") (name "Net-(K55A-CA)") (class "Default")
      (node (ref "K55") (pin "3") (pinfunction "CA_3") (pintype "passive"))
      (node (ref "X30") (pin "28") (pinfunction "28_28") (pintype "passive"))
    )
    (net (code "198") (name "Net-(K55A-CB)") (class "Default")
      (node (ref "K55") (pin "4") (pinfunction "CB_4") (pintype "passive"))
      (node (ref "X28") (pin "28") (pinfunction "28_28") (pintype "passive"))
    )
    (net (code "199") (name "Net-(K55B--)") (class "Default")
      (node (ref "K55") (pin "2") (pinfunction "-_2") (pintype "passive"))
      (node (ref "Q56") (pin "3") (pinfunction "D_3") (pintype "passive"))
    )
    (net (code "200") (name "Net-(K56A-CA)") (class "Default")
      (node (ref "K56") (pin "3") (pinfunction "CA_3") (pintype "passive"))
      (node (ref "X30") (pin "29") (pinfunction "29_29") (pintype "passive"))
    )
    (net (code "201") (name "Net-(K56A-CB)") (class "Default")
      (node (ref "K56") (pin "4") (pinfunction "CB_4") (pintype "passive"))
      (node (ref "X28") (pin "29") (pinfunction "29_29") (pintype "passive"))
    )
    (net (code "202") (name "Net-(K56B--)") (class "Default")
      (node (ref "K56") (pin "2") (pinfunction "-_2") (pintype "passive"))
      (node (ref "Q57") (pin "3") (pinfunction "D_3") (pintype "passive"))
    )
    (net (code "203") (name "Net-(K57A-CA)") (class "Default")
      (node (ref "K57") (pin "3") (pinfunction "CA_3") (pintype "passive"))
      (node (ref "X30") (pin "30") (pinfunction "30_30") (pintype "passive"))
    )
    (net (code "204") (name "Net-(K57A-CB)") (class "Default")
      (node (ref "K57") (pin "4") (pinfunction "CB_4") (pintype "passive"))
      (node (ref "X28") (pin "30") (pinfunction "30_30") (pintype "passive"))
    )
    (net (code "205") (name "Net-(K57B--)") (class "Default")
      (node (ref "K57") (pin "2") (pinfunction "-_2") (pintype "passive"))
      (node (ref "Q58") (pin "3") (pinfunction "D_3") (pintype "passive"))
    )
    (net (code "206") (name "Net-(K58A-CA)") (class "Default")
      (node (ref "K58") (pin "3") (pinfunction "CA_3") (pintype "passive"))
      (node (ref "X30") (pin "31") (pinfunction "31_31") (pintype "passive"))
    )
    (net (code "207") (name "Net-(K58A-CB)") (class "Default")
      (node (ref "K58") (pin "4") (pinfunction "CB_4") (pintype "passive"))
      (node (ref "X28") (pin "31") (pinfunction "31_31") (pintype "passive"))
    )
    (net (code "208") (name "Net-(K58B--)") (class "Default")
      (node (ref "K58") (pin "2") (pinfunction "-_2") (pintype "passive"))
      (node (ref "Q59") (pin "3") (pinfunction "D_3") (pintype "passive"))
    )
    (net (code "209") (name "Net-(K59A-CA)") (class "Default")
      (node (ref "K59") (pin "3") (pinfunction "CA_3") (pintype "passive"))
      (node (ref "X30") (pin "32") (pinfunction "32_32") (pintype "passive"))
    )
    (net (code "210") (name "Net-(K59A-CB)") (class "Default")
      (node (ref "K59") (pin "4") (pinfunction "CB_4") (pintype "passive"))
      (node (ref "X28") (pin "32") (pinfunction "32_32") (pintype "passive"))
    )
    (net (code "211") (name "Net-(K59B--)") (class "Default")
      (node (ref "K59") (pin "2") (pinfunction "-_2") (pintype "passive"))
      (node (ref "Q60") (pin "3") (pinfunction "D_3") (pintype "passive"))
    )
    (net (code "212") (name "Net-(K60A-CA)") (class "Default")
      (node (ref "K60") (pin "3") (pinfunction "CA_3") (pintype "passive"))
      (node (ref "X30") (pin "33") (pinfunction "33_33") (pintype "passive"))
    )
    (net (code "213") (name "Net-(K60A-CB)") (class "Default")
      (node (ref "K60") (pin "4") (pinfunction "CB_4") (pintype "passive"))
      (node (ref "X28") (pin "33") (pinfunction "33_33") (pintype "passive"))
    )
    (net (code "214") (name "Net-(K60B--)") (class "Default")
      (node (ref "K60") (pin "2") (pinfunction "-_2") (pintype "passive"))
      (node (ref "Q61") (pin "3") (pinfunction "D_3") (pintype "passive"))
    )
    (net (code "215") (name "Net-(K61A-CA)") (class "Default")
      (node (ref "K61") (pin "3") (pinfunction "CA_3") (pintype "passive"))
      (node (ref "X30") (pin "34") (pinfunction "34_34") (pintype "passive"))
    )
    (net (code "216") (name "Net-(K61A-CB)") (class "Default")
      (node (ref "K61") (pin "4") (pinfunction "CB_4") (pintype "passive"))
      (node (ref "X28") (pin "34") (pinfunction "34_34") (pintype "passive"))
    )
    (net (code "217") (name "Net-(K61B--)") (class "Default")
      (node (ref "K61") (pin "2") (pinfunction "-_2") (pintype "passive"))
      (node (ref "Q62") (pin "3") (pinfunction "D_3") (pintype "passive"))
    )
    (net (code "218") (name "Net-(K62A-CA)") (class "Default")
      (node (ref "K62") (pin "3") (pinfunction "CA_3") (pintype "passive"))
      (node (ref "X30") (pin "35") (pinfunction "35_35") (pintype "passive"))
    )
    (net (code "219") (name "Net-(K62A-CB)") (class "Default")
      (node (ref "K62") (pin "4") (pinfunction "CB_4") (pintype "passive"))
      (node (ref "X28") (pin "35") (pinfunction "35_35") (pintype "passive"))
    )
    (net (code "220") (name "Net-(K62B--)") (class "Default")
      (node (ref "K62") (pin "2") (pinfunction "-_2") (pintype "passive"))
      (node (ref "Q63") (pin "3") (pinfunction "D_3") (pintype "passive"))
    )
    (net (code "221") (name "Net-(K63A-CA)") (class "Default")
      (node (ref "K63") (pin "3") (pinfunction "CA_3") (pintype "passive"))
      (node (ref "X30") (pin "36") (pinfunction "36_36") (pintype "passive"))
    )
    (net (code "222") (name "Net-(K63A-CB)") (class "Default")
      (node (ref "K63") (pin "4") (pinfunction "CB_4") (pintype "passive"))
      (node (ref "X28") (pin "36") (pinfunction "36_36") (pintype "passive"))
    )
    (net (code "223") (name "Net-(K63B--)") (class "Default")
      (node (ref "K63") (pin "2") (pinfunction "-_2") (pintype "passive"))
      (node (ref "Q64") (pin "3") (pinfunction "D_3") (pintype "passive"))
    )
    (net (code "224") (name "Net-(K64A-CA)") (class "Default")
      (node (ref "K64") (pin "3") (pinfunction "CA_3") (pintype "passive"))
      (node (ref "X30") (pin "37") (pinfunction "37_37") (pintype "passive"))
    )
    (net (code "225") (name "Net-(K64A-CB)") (class "Default")
      (node (ref "K64") (pin "4") (pinfunction "CB_4") (pintype "passive"))
      (node (ref "X28") (pin "37") (pinfunction "37_37") (pintype "passive"))
    )
    (net (code "226") (name "Net-(K64B--)") (class "Default")
      (node (ref "K64") (pin "2") (pinfunction "-_2") (pintype "passive"))
      (node (ref "Q65") (pin "3") (pinfunction "D_3") (pintype "passive"))
    )
    (net (code "227") (name "Net-(K65A-CA)") (class "Default")
      (node (ref "K65") (pin "3") (pinfunction "CA_3") (pintype "passive"))
      (node (ref "X30") (pin "38") (pinfunction "38_38") (pintype "passive"))
    )
    (net (code "228") (name "Net-(K65A-CB)") (class "Default")
      (node (ref "K65") (pin "4") (pinfunction "CB_4") (pintype "passive"))
      (node (ref "X28") (pin "38") (pinfunction "38_38") (pintype "passive"))
    )
    (net (code "229") (name "Net-(K65B--)") (class "Default")
      (node (ref "K65") (pin "2") (pinfunction "-_2") (pintype "passive"))
      (node (ref "Q66") (pin "3") (pinfunction "D_3") (pintype "passive"))
    )
    (net (code "230") (name "Net-(K66A-CA)") (class "Default")
      (node (ref "K66") (pin "3") (pinfunction "CA_3") (pintype "passive"))
      (node (ref "X30") (pin "39") (pinfunction "39_39") (pintype "passive"))
    )
    (net (code "231") (name "Net-(K66A-CB)") (class "Default")
      (node (ref "K66") (pin "4") (pinfunction "CB_4") (pintype "passive"))
      (node (ref "X28") (pin "39") (pinfunction "39_39") (pintype "passive"))
    )
    (net (code "232") (name "Net-(K66B--)") (class "Default")
      (node (ref "K66") (pin "2") (pinfunction "-_2") (pintype "passive"))
      (node (ref "Q67") (pin "3") (pinfunction "D_3") (pintype "passive"))
    )
    (net (code "233") (name "Net-(K67A-CA)") (class "Default")
      (node (ref "K67") (pin "3") (pinfunction "CA_3") (pintype "passive"))
      (node (ref "X30") (pin "40") (pinfunction "40_40") (pintype "passive"))
    )
    (net (code "234") (name "Net-(K67A-CB)") (class "Default")
      (node (ref "K67") (pin "4") (pinfunction "CB_4") (pintype "passive"))
      (node (ref "X28") (pin "40") (pinfunction "40_40") (pintype "passive"))
    )
    (net (code "235") (name "Net-(K67B--)") (class "Default")
      (node (ref "K67") (pin "2") (pinfunction "-_2") (pintype "passive"))
      (node (ref "Q68") (pin "3") (pinfunction "D_3") (pintype "passive"))
    )
    (net (code "236") (name "Net-(K68A-CA)") (class "Default")
      (node (ref "K68") (pin "3") (pinfunction "CA_3") (pintype "passive"))
      (node (ref "X30") (pin "41") (pinfunction "41_41") (pintype "passive"))
    )
    (net (code "237") (name "Net-(K68A-CB)") (class "Default")
      (node (ref "K68") (pin "4") (pinfunction "CB_4") (pintype "passive"))
      (node (ref "X28") (pin "41") (pinfunction "41_41") (pintype "passive"))
    )
    (net (code "238") (name "Net-(K68B--)") (class "Default")
      (node (ref "K68") (pin "2") (pinfunction "-_2") (pintype "passive"))
      (node (ref "Q69") (pin "3") (pinfunction "D_3") (pintype "passive"))
    )
    (net (code "239") (name "Net-(K69A-CA)") (class "Default")
      (node (ref "K69") (pin "3") (pinfunction "CA_3") (pintype "passive"))
      (node (ref "X30") (pin "42") (pinfunction "42_42") (pintype "passive"))
    )
    (net (code "240") (name "Net-(K69A-CB)") (class "Default")
      (node (ref "K69") (pin "4") (pinfunction "CB_4") (pintype "passive"))
      (node (ref "X28") (pin "42") (pinfunction "42_42") (pintype "passive"))
    )
    (net (code "241") (name "Net-(K69B--)") (class "Default")
      (node (ref "K69") (pin "2") (pinfunction "-_2") (pintype "passive"))
      (node (ref "Q70") (pin "3") (pinfunction "D_3") (pintype "passive"))
    )
    (net (code "242") (name "Net-(K70A-CA)") (class "Default")
      (node (ref "K70") (pin "3") (pinfunction "CA_3") (pintype "passive"))
      (node (ref "X30") (pin "43") (pinfunction "43_43") (pintype "passive"))
    )
    (net (code "243") (name "Net-(K70A-CB)") (class "Default")
      (node (ref "K70") (pin "4") (pinfunction "CB_4") (pintype "passive"))
      (node (ref "X28") (pin "43") (pinfunction "43_43") (pintype "passive"))
    )
    (net (code "244") (name "Net-(K70B--)") (class "Default")
      (node (ref "K70") (pin "2") (pinfunction "-_2") (pintype "passive"))
      (node (ref "Q71") (pin "3") (pinfunction "D_3") (pintype "passive"))
    )
    (net (code "245") (name "Net-(K71A-CA)") (class "Default")
      (node (ref "K71") (pin "3") (pinfunction "CA_3") (pintype "passive"))
      (node (ref "X30") (pin "44") (pinfunction "44_44") (pintype "passive"))
    )
    (net (code "246") (name "Net-(K71A-CB)") (class "Default")
      (node (ref "K71") (pin "4") (pinfunction "CB_4") (pintype "passive"))
      (node (ref "X28") (pin "44") (pinfunction "44_44") (pintype "passive"))
    )
    (net (code "247") (name "Net-(K71B--)") (class "Default")
      (node (ref "K71") (pin "2") (pinfunction "-_2") (pintype "passive"))
      (node (ref "Q72") (pin "3") (pinfunction "D_3") (pintype "passive"))
    )
    (net (code "248") (name "Net-(K72A-CA)") (class "Default")
      (node (ref "K72") (pin "3") (pinfunction "CA_3") (pintype "passive"))
      (node (ref "X30") (pin "45") (pinfunction "45_45") (pintype "passive"))
    )
    (net (code "249") (name "Net-(K72A-CB)") (class "Default")
      (node (ref "K72") (pin "4") (pinfunction "CB_4") (pintype "passive"))
      (node (ref "X28") (pin "45") (pinfunction "45_45") (pintype "passive"))
    )
    (net (code "250") (name "Net-(K72B--)") (class "Default")
      (node (ref "K72") (pin "2") (pinfunction "-_2") (pintype "passive"))
      (node (ref "Q73") (pin "3") (pinfunction "D_3") (pintype "passive"))
    )
    (net (code "251") (name "Net-(K73A-CA)") (class "Default")
      (node (ref "K73") (pin "3") (pinfunction "CA_3") (pintype "passive"))
      (node (ref "X30") (pin "46") (pinfunction "46_46") (pintype "passive"))
    )
    (net (code "252") (name "Net-(K73A-CB)") (class "Default")
      (node (ref "K73") (pin "4") (pinfunction "CB_4") (pintype "passive"))
      (node (ref "X28") (pin "46") (pinfunction "46_46") (pintype "passive"))
    )
    (net (code "253") (name "Net-(K73B--)") (class "Default")
      (node (ref "K73") (pin "2") (pinfunction "-_2") (pintype "passive"))
      (node (ref "Q74") (pin "3") (pinfunction "D_3") (pintype "passive"))
    )
    (net (code "254") (name "Net-(K74A-CA)") (class "Default")
      (node (ref "K74") (pin "3") (pinfunction "CA_3") (pintype "passive"))
      (node (ref "X30") (pin "47") (pinfunction "47_47") (pintype "passive"))
    )
    (net (code "255") (name "Net-(K74A-CB)") (class "Default")
      (node (ref "K74") (pin "4") (pinfunction "CB_4") (pintype "passive"))
      (node (ref "X28") (pin "47") (pinfunction "47_47") (pintype "passive"))
    )
    (net (code "256") (name "Net-(K74B--)") (class "Default")
      (node (ref "K74") (pin "2") (pinfunction "-_2") (pintype "passive"))
      (node (ref "Q75") (pin "3") (pinfunction "D_3") (pintype "passive"))
    )
    (net (code "257") (name "Net-(K75A-CA)") (class "Default")
      (node (ref "K75") (pin "3") (pinfunction "CA_3") (pintype "passive"))
      (node (ref "X30") (pin "48") (pinfunction "48_48") (pintype "passive"))
    )
    (net (code "258") (name "Net-(K75A-CB)") (class "Default")
      (node (ref "K75") (pin "4") (pinfunction "CB_4") (pintype "passive"))
      (node (ref "X28") (pin "48") (pinfunction "48_48") (pintype "passive"))
    )
    (net (code "259") (name "Net-(K75B--)") (class "Default")
      (node (ref "K75") (pin "2") (pinfunction "-_2") (pintype "passive"))
      (node (ref "Q76") (pin "3") (pinfunction "D_3") (pintype "passive"))
    )
    (net (code "260") (name "Net-(K76A-CA)") (class "Default")
      (node (ref "K76") (pin "3") (pinfunction "CA_3") (pintype "passive"))
      (node (ref "X30") (pin "49") (pinfunction "49_49") (pintype "passive"))
    )
    (net (code "261") (name "Net-(K76A-CB)") (class "Default")
      (node (ref "K76") (pin "4") (pinfunction "CB_4") (pintype "passive"))
      (node (ref "X28") (pin "49") (pinfunction "49_49") (pintype "passive"))
    )
    (net (code "262") (name "Net-(K76B--)") (class "Default")
      (node (ref "K76") (pin "2") (pinfunction "-_2") (pintype "passive"))
      (node (ref "Q81") (pin "3") (pinfunction "D_3") (pintype "passive"))
    )
    (net (code "263") (name "Net-(K77A-CA)") (class "Default")
      (node (ref "K77") (pin "3") (pinfunction "CA_3") (pintype "passive"))
      (node (ref "X30") (pin "50") (pinfunction "50_50") (pintype "passive"))
    )
    (net (code "264") (name "Net-(K77A-CB)") (class "Default")
      (node (ref "K77") (pin "4") (pinfunction "CB_4") (pintype "passive"))
      (node (ref "X28") (pin "50") (pinfunction "50_50") (pintype "passive"))
    )
    (net (code "265") (name "Net-(K77B--)") (class "Default")
      (node (ref "K77") (pin "2") (pinfunction "-_2") (pintype "passive"))
      (node (ref "Q82") (pin "3") (pinfunction "D_3") (pintype "passive"))
    )
    (net (code "266") (name "Net-(K78A-CA)") (class "Default")
      (node (ref "K78") (pin "3") (pinfunction "CA_3") (pintype "passive"))
      (node (ref "X30") (pin "51") (pinfunction "51_51") (pintype "passive"))
    )
    (net (code "267") (name "Net-(K78A-CB)") (class "Default")
      (node (ref "K78") (pin "4") (pinfunction "CB_4") (pintype "passive"))
      (node (ref "X28") (pin "51") (pinfunction "51_51") (pintype "passive"))
    )
    (net (code "268") (name "Net-(K78B--)") (class "Default")
      (node (ref "K78") (pin "2") (pinfunction "-_2") (pintype "passive"))
      (node (ref "Q83") (pin "3") (pinfunction "D_3") (pintype "passive"))
    )
    (net (code "269") (name "Net-(K79A-CA)") (class "Default")
      (node (ref "K79") (pin "3") (pinfunction "CA_3") (pintype "passive"))
      (node (ref "X30") (pin "52") (pinfunction "52_52") (pintype "passive"))
    )
    (net (code "270") (name "Net-(K79A-CB)") (class "Default")
      (node (ref "K79") (pin "4") (pinfunction "CB_4") (pintype "passive"))
      (node (ref "X28") (pin "52") (pinfunction "52_52") (pintype "passive"))
    )
    (net (code "271") (name "Net-(K79B--)") (class "Default")
      (node (ref "K79") (pin "2") (pinfunction "-_2") (pintype "passive"))
      (node (ref "Q84") (pin "3") (pinfunction "D_3") (pintype "passive"))
    )
    (net (code "272") (name "Net-(K80A-CA)") (class "Default")
      (node (ref "K80") (pin "3") (pinfunction "CA_3") (pintype "passive"))
      (node (ref "X30") (pin "53") (pinfunction "53_53") (pintype "passive"))
    )
    (net (code "273") (name "Net-(K80A-CB)") (class "Default")
      (node (ref "K80") (pin "4") (pinfunction "CB_4") (pintype "passive"))
      (node (ref "X28") (pin "53") (pinfunction "53_53") (pintype "passive"))
    )
    (net (code "274") (name "Net-(K80B--)") (class "Default")
      (node (ref "K80") (pin "2") (pinfunction "-_2") (pintype "passive"))
      (node (ref "Q85") (pin "3") (pinfunction "D_3") (pintype "passive"))
    )
    (net (code "275") (name "Net-(K81A-CA)") (class "Default")
      (node (ref "K81") (pin "3") (pinfunction "CA_3") (pintype "passive"))
      (node (ref "X30") (pin "54") (pinfunction "54_54") (pintype "passive"))
    )
    (net (code "276") (name "Net-(K81A-CB)") (class "Default")
      (node (ref "K81") (pin "4") (pinfunction "CB_4") (pintype "passive"))
      (node (ref "X28") (pin "54") (pinfunction "54_54") (pintype "passive"))
    )
    (net (code "277") (name "Net-(K81B--)") (class "Default")
      (node (ref "K81") (pin "2") (pinfunction "-_2") (pintype "passive"))
      (node (ref "Q86") (pin "3") (pinfunction "D_3") (pintype "passive"))
    )
    (net (code "278") (name "Net-(K82A-CA)") (class "Default")
      (node (ref "K82") (pin "3") (pinfunction "CA_3") (pintype "passive"))
      (node (ref "X30") (pin "55") (pinfunction "55_55") (pintype "passive"))
    )
    (net (code "279") (name "Net-(K82A-CB)") (class "Default")
      (node (ref "K82") (pin "4") (pinfunction "CB_4") (pintype "passive"))
      (node (ref "X28") (pin "55") (pinfunction "55_55") (pintype "passive"))
    )
    (net (code "280") (name "Net-(K82B--)") (class "Default")
      (node (ref "K82") (pin "2") (pinfunction "-_2") (pintype "passive"))
      (node (ref "Q87") (pin "3") (pinfunction "D_3") (pintype "passive"))
    )
    (net (code "281") (name "Net-(K83A-CA)") (class "Default")
      (node (ref "K83") (pin "3") (pinfunction "CA_3") (pintype "passive"))
      (node (ref "X30") (pin "56") (pinfunction "56_56") (pintype "passive"))
    )
    (net (code "282") (name "Net-(K83A-CB)") (class "Default")
      (node (ref "K83") (pin "4") (pinfunction "CB_4") (pintype "passive"))
      (node (ref "X28") (pin "56") (pinfunction "56_56") (pintype "passive"))
    )
    (net (code "283") (name "Net-(K83B--)") (class "Default")
      (node (ref "K83") (pin "2") (pinfunction "-_2") (pintype "passive"))
      (node (ref "Q88") (pin "3") (pinfunction "D_3") (pintype "passive"))
    )
    (net (code "284") (name "Net-(K84A-CA)") (class "Default")
      (node (ref "K84") (pin "3") (pinfunction "CA_3") (pintype "passive"))
      (node (ref "X30") (pin "57") (pinfunction "57_57") (pintype "passive"))
    )
    (net (code "285") (name "Net-(K84A-CB)") (class "Default")
      (node (ref "K84") (pin "4") (pinfunction "CB_4") (pintype "passive"))
      (node (ref "X28") (pin "57") (pinfunction "57_57") (pintype "passive"))
    )
    (net (code "286") (name "Net-(K84B--)") (class "Default")
      (node (ref "K84") (pin "2") (pinfunction "-_2") (pintype "passive"))
      (node (ref "Q89") (pin "3") (pinfunction "D_3") (pintype "passive"))
    )
    (net (code "287") (name "Net-(K85A-CA)") (class "Default")
      (node (ref "K85") (pin "3") (pinfunction "CA_3") (pintype "passive"))
      (node (ref "X30") (pin "58") (pinfunction "58_58") (pintype "passive"))
    )
    (net (code "288") (name "Net-(K85A-CB)") (class "Default")
      (node (ref "K85") (pin "4") (pinfunction "CB_4") (pintype "passive"))
      (node (ref "X28") (pin "58") (pinfunction "58_58") (pintype "passive"))
    )
    (net (code "289") (name "Net-(K85B--)") (class "Default")
      (node (ref "K85") (pin "2") (pinfunction "-_2") (pintype "passive"))
      (node (ref "Q90") (pin "3") (pinfunction "D_3") (pintype "passive"))
    )
    (net (code "290") (name "Net-(K86A-CA)") (class "Default")
      (node (ref "K86") (pin "3") (pinfunction "CA_3") (pintype "passive"))
      (node (ref "X30") (pin "59") (pinfunction "59_59") (pintype "passive"))
    )
    (net (code "291") (name "Net-(K86A-CB)") (class "Default")
      (node (ref "K86") (pin "4") (pinfunction "CB_4") (pintype "passive"))
      (node (ref "X28") (pin "59") (pinfunction "59_59") (pintype "passive"))
    )
    (net (code "292") (name "Net-(K86B--)") (class "Default")
      (node (ref "K86") (pin "2") (pinfunction "-_2") (pintype "passive"))
      (node (ref "Q91") (pin "3") (pinfunction "D_3") (pintype "passive"))
    )
    (net (code "293") (name "Net-(K87A-CA)") (class "Default")
      (node (ref "K87") (pin "3") (pinfunction "CA_3") (pintype "passive"))
      (node (ref "X30") (pin "60") (pinfunction "60_60") (pintype "passive"))
    )
    (net (code "294") (name "Net-(K87A-CB)") (class "Default")
      (node (ref "K87") (pin "4") (pinfunction "CB_4") (pintype "passive"))
      (node (ref "X28") (pin "60") (pinfunction "60_60") (pintype "passive"))
    )
    (net (code "295") (name "Net-(K87B--)") (class "Default")
      (node (ref "K87") (pin "2") (pinfunction "-_2") (pintype "passive"))
      (node (ref "Q92") (pin "3") (pinfunction "D_3") (pintype "passive"))
    )
    (net (code "296") (name "Net-(K88A-CA)") (class "Default")
      (node (ref "K88") (pin "3") (pinfunction "CA_3") (pintype "passive"))
      (node (ref "X30") (pin "61") (pinfunction "61_61") (pintype "passive"))
    )
    (net (code "297") (name "Net-(K88A-CB)") (class "Default")
      (node (ref "K88") (pin "4") (pinfunction "CB_4") (pintype "passive"))
      (node (ref "X28") (pin "61") (pinfunction "61_61") (pintype "passive"))
    )
    (net (code "298") (name "Net-(K88B--)") (class "Default")
      (node (ref "K88") (pin "2") (pinfunction "-_2") (pintype "passive"))
      (node (ref "Q93") (pin "3") (pinfunction "D_3") (pintype "passive"))
    )
    (net (code "299") (name "Net-(K89A-CA)") (class "Default")
      (node (ref "K89") (pin "3") (pinfunction "CA_3") (pintype "passive"))
      (node (ref "X30") (pin "62") (pinfunction "62_62") (pintype "passive"))
    )
    (net (code "300") (name "Net-(K89A-CB)") (class "Default")
      (node (ref "K89") (pin "4") (pinfunction "CB_4") (pintype "passive"))
      (node (ref "X28") (pin "62") (pinfunction "62_62") (pintype "passive"))
    )
    (net (code "301") (name "Net-(K89B--)") (class "Default")
      (node (ref "K89") (pin "2") (pinfunction "-_2") (pintype "passive"))
      (node (ref "Q94") (pin "3") (pinfunction "D_3") (pintype "passive"))
    )
    (net (code "302") (name "Net-(K90A-CA)") (class "Default")
      (node (ref "K90") (pin "3") (pinfunction "CA_3") (pintype "passive"))
      (node (ref "X30") (pin "63") (pinfunction "63_63") (pintype "passive"))
    )
    (net (code "303") (name "Net-(K90A-CB)") (class "Default")
      (node (ref "K90") (pin "4") (pinfunction "CB_4") (pintype "passive"))
      (node (ref "X28") (pin "63") (pinfunction "63_63") (pintype "passive"))
    )
    (net (code "304") (name "Net-(K90B--)") (class "Default")
      (node (ref "K90") (pin "2") (pinfunction "-_2") (pintype "passive"))
      (node (ref "Q95") (pin "3") (pinfunction "D_3") (pintype "passive"))
    )
    (net (code "305") (name "Net-(K91A-CA)") (class "Default")
      (node (ref "K91") (pin "3") (pinfunction "CA_3") (pintype "passive"))
      (node (ref "X30") (pin "64") (pinfunction "64_64") (pintype "passive"))
    )
    (net (code "306") (name "Net-(K91A-CB)") (class "Default")
      (node (ref "K91") (pin "4") (pinfunction "CB_4") (pintype "passive"))
      (node (ref "X28") (pin "64") (pinfunction "64_64") (pintype "passive"))
    )
    (net (code "307") (name "Net-(K91B--)") (class "Default")
      (node (ref "K91") (pin "2") (pinfunction "-_2") (pintype "passive"))
      (node (ref "Q96") (pin "3") (pinfunction "D_3") (pintype "passive"))
    )
  )
)
